# SOC_LPC1787.net
KiCad netlist of a schematic drawn in Altium Designer
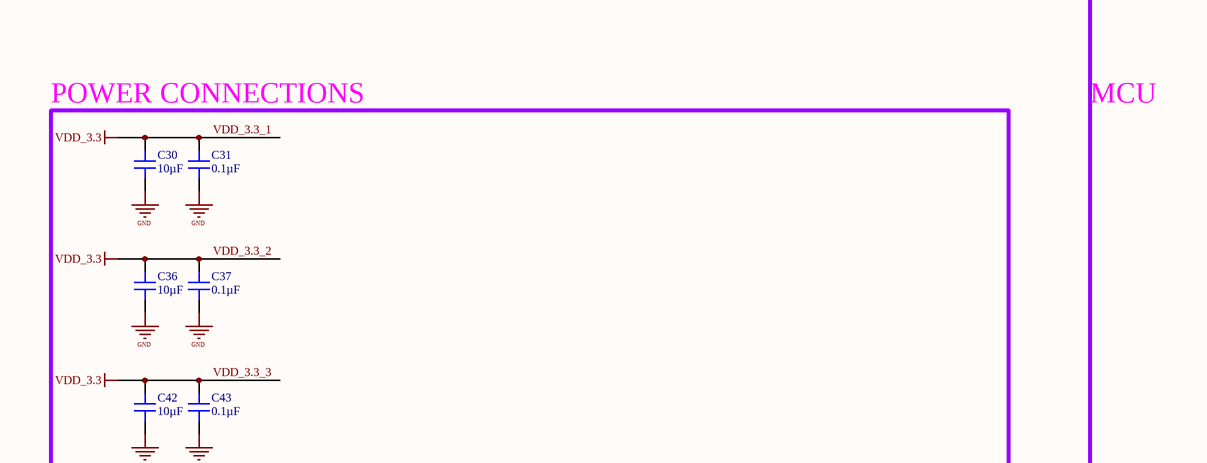
[diagram p0: SOC LPC1787.SchDoc, top left]
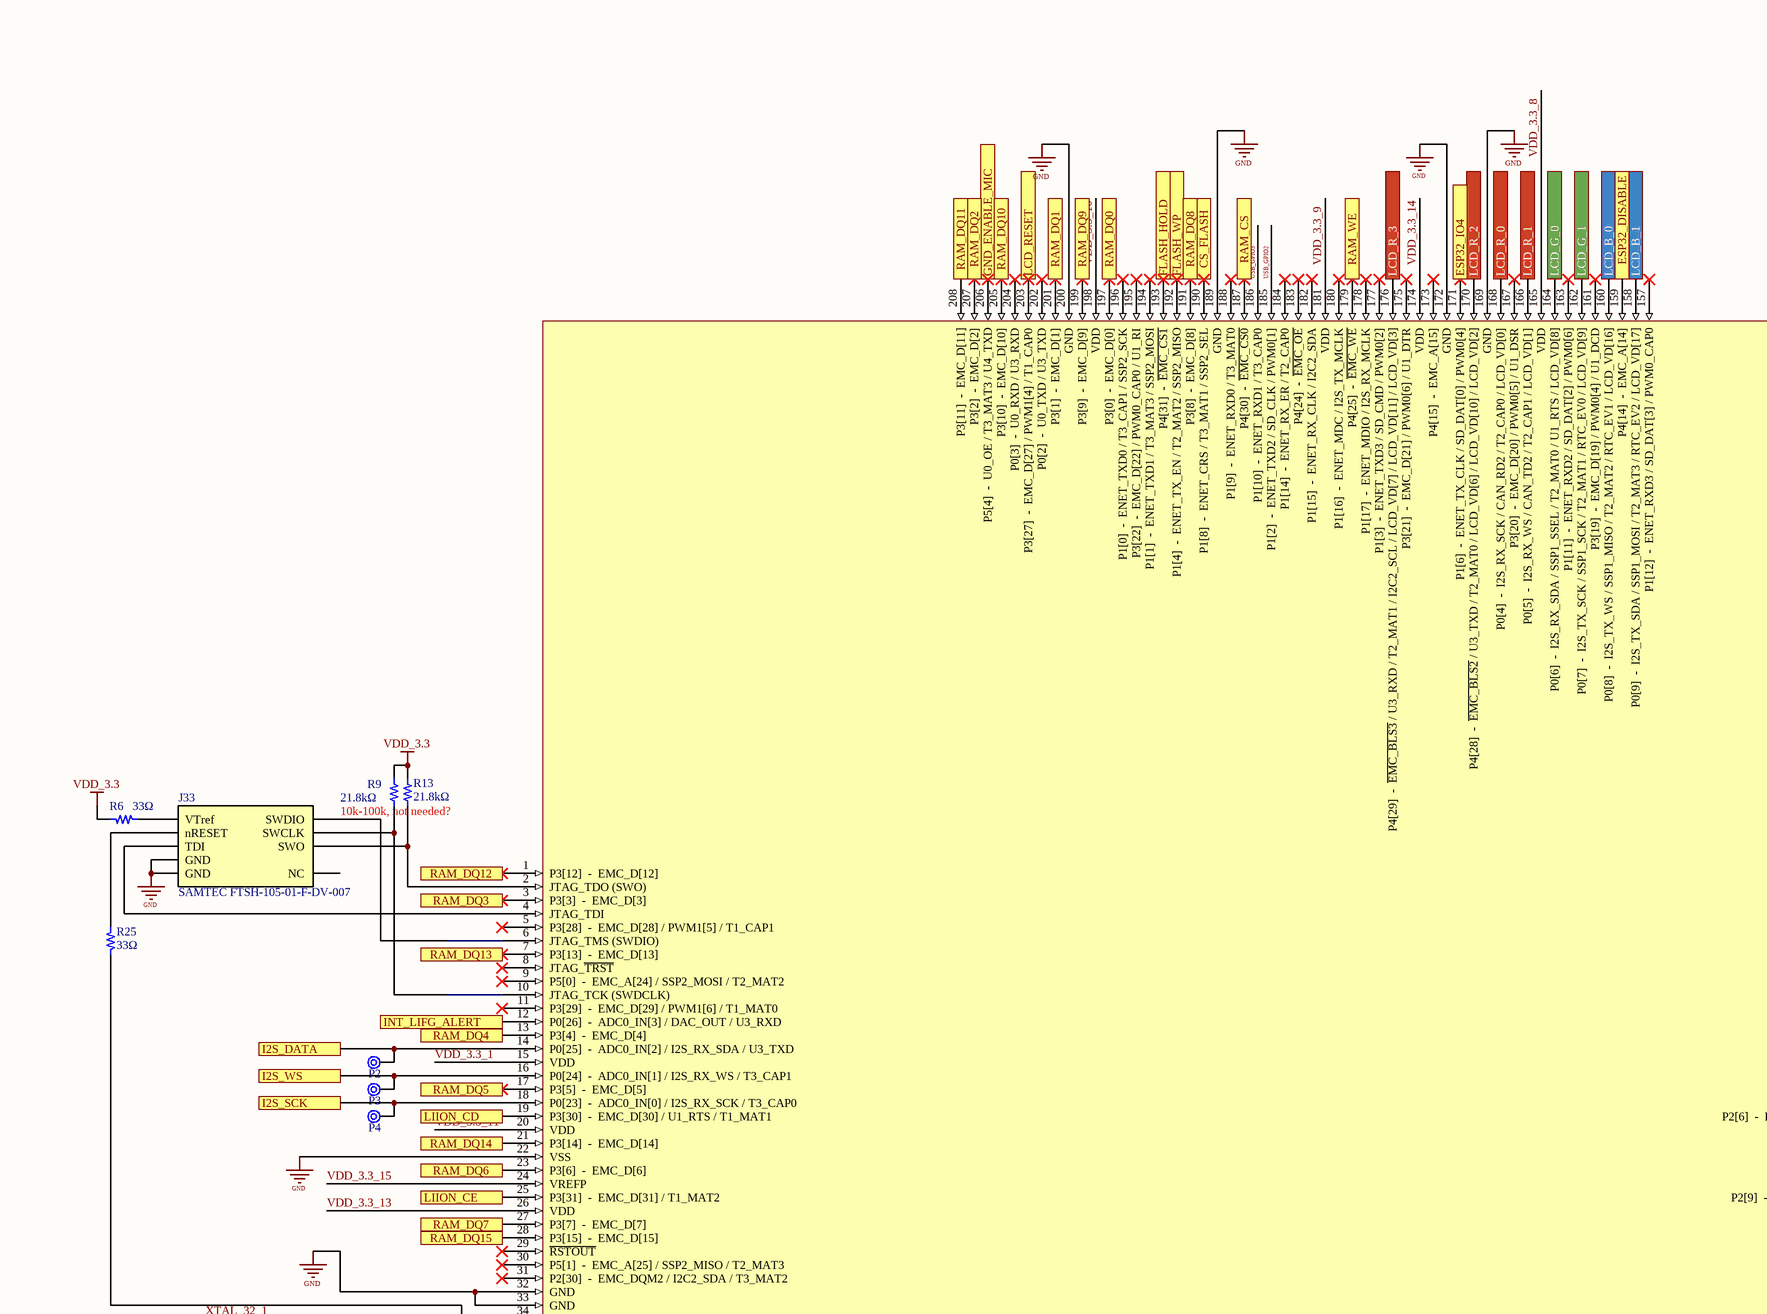
[diagram p1: SOC LPC1787.SchDoc, top middle]
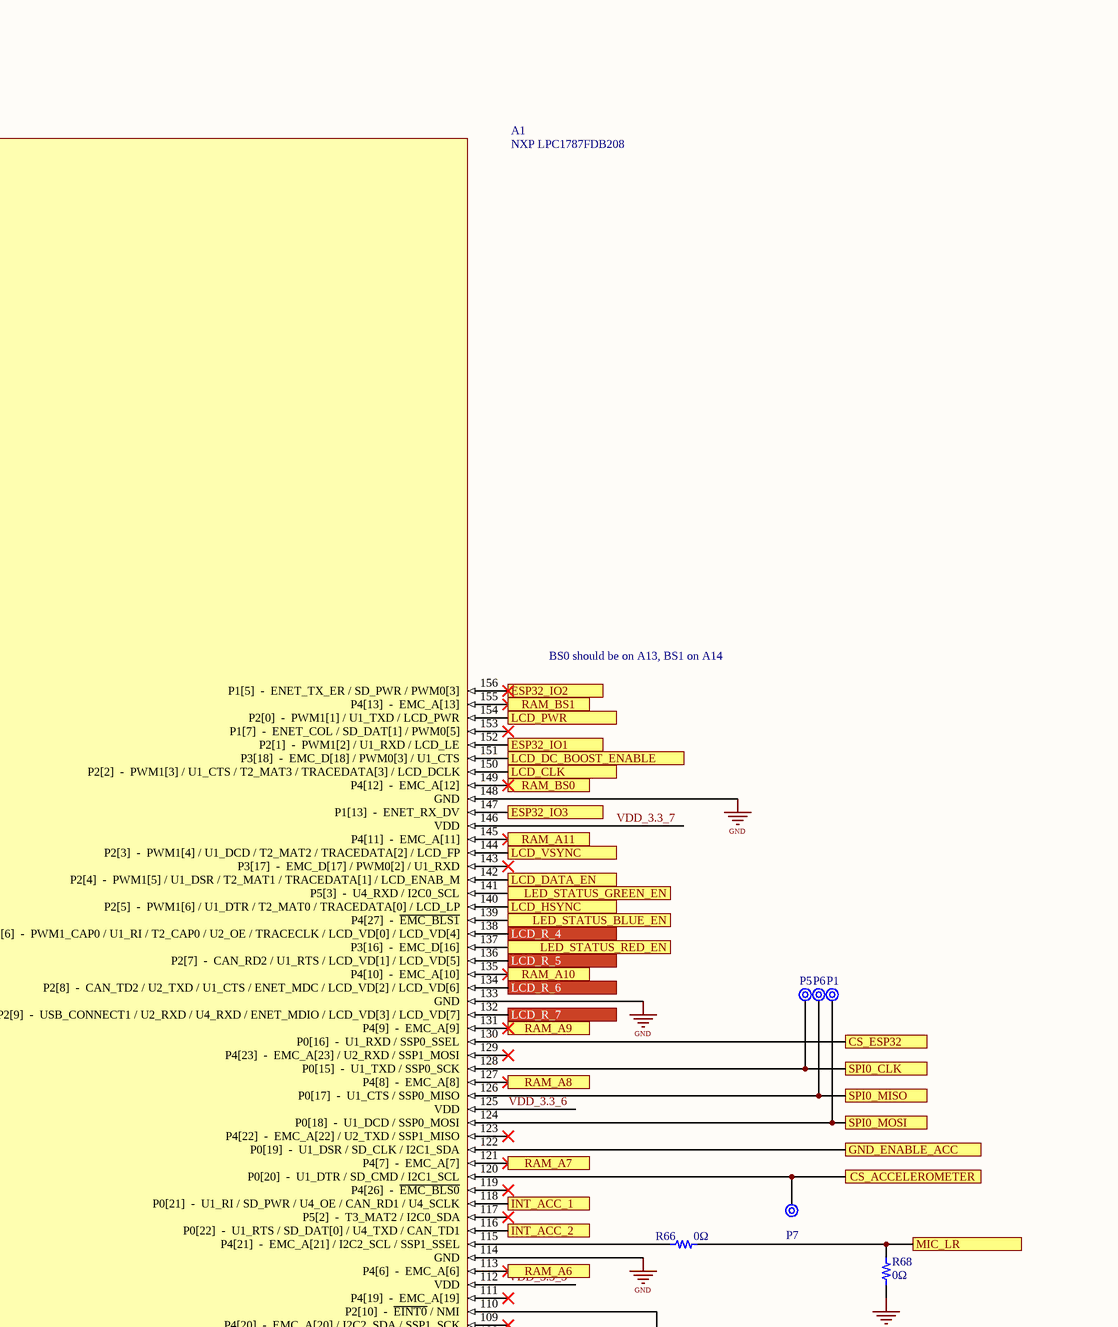
[diagram p2: SOC LPC1787.SchDoc, top right]
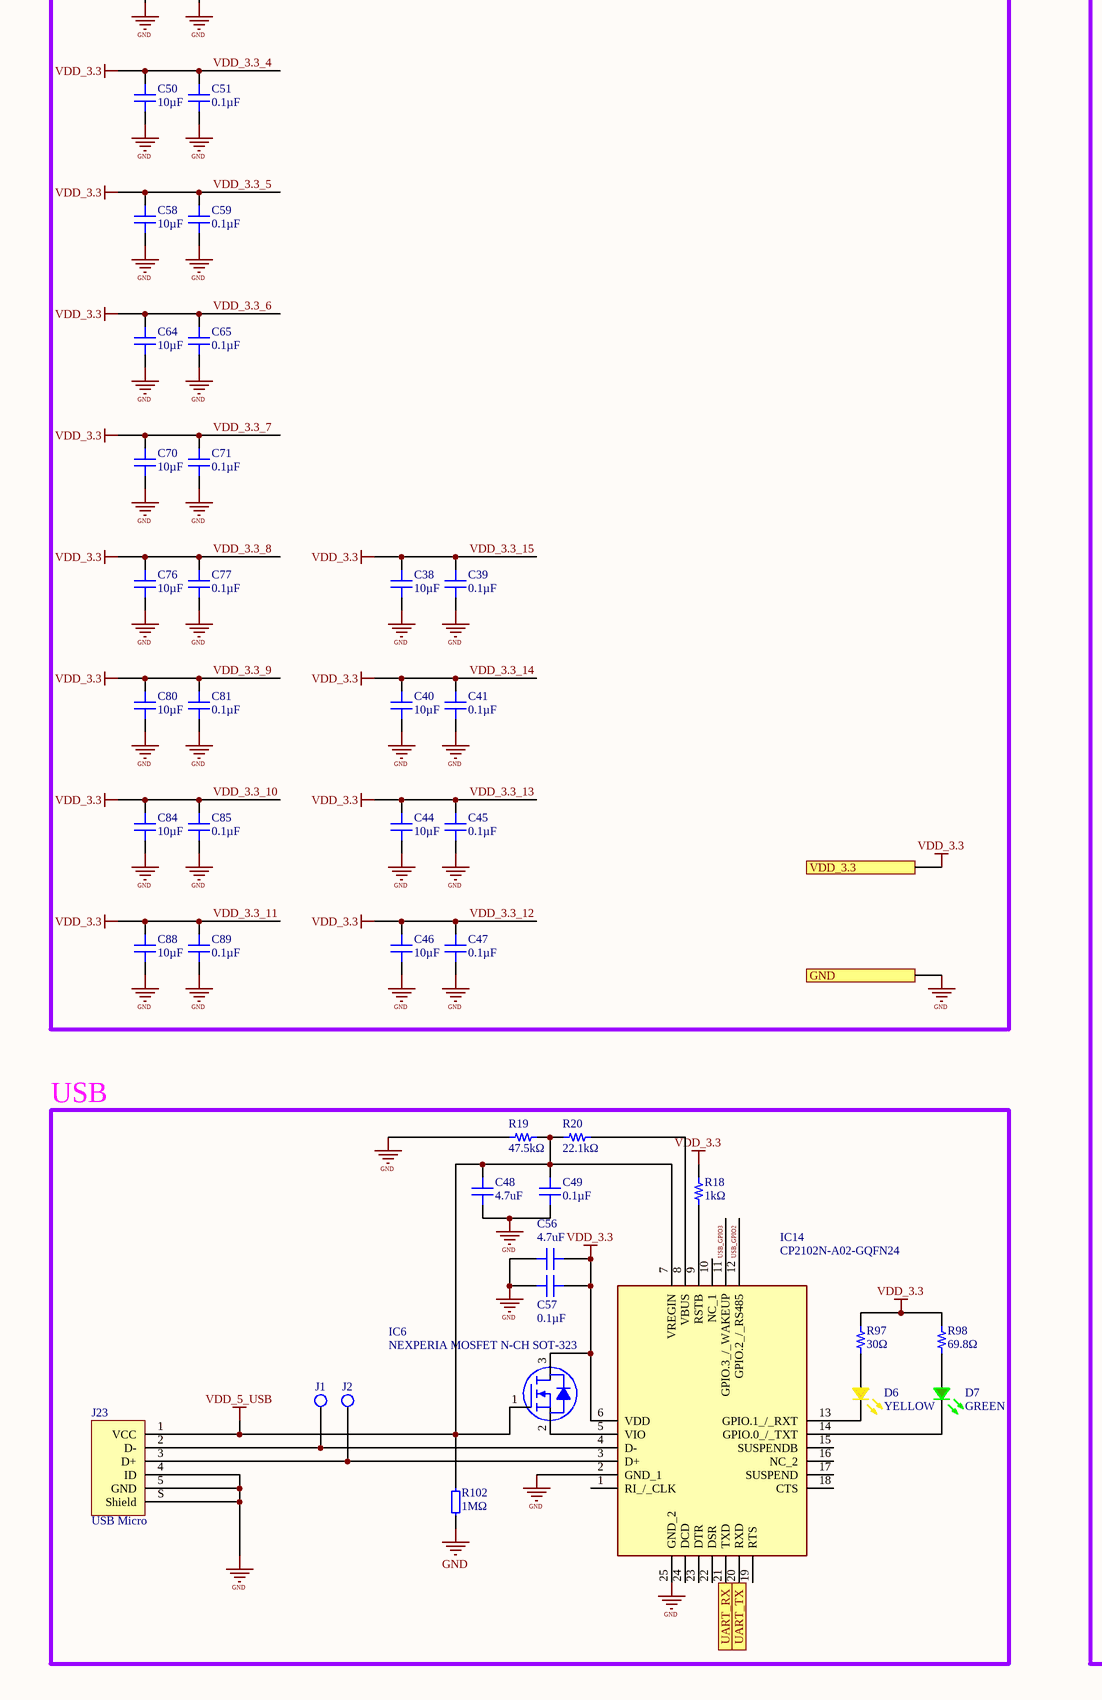
[diagram p3: SOC LPC1787.SchDoc, bottom left]
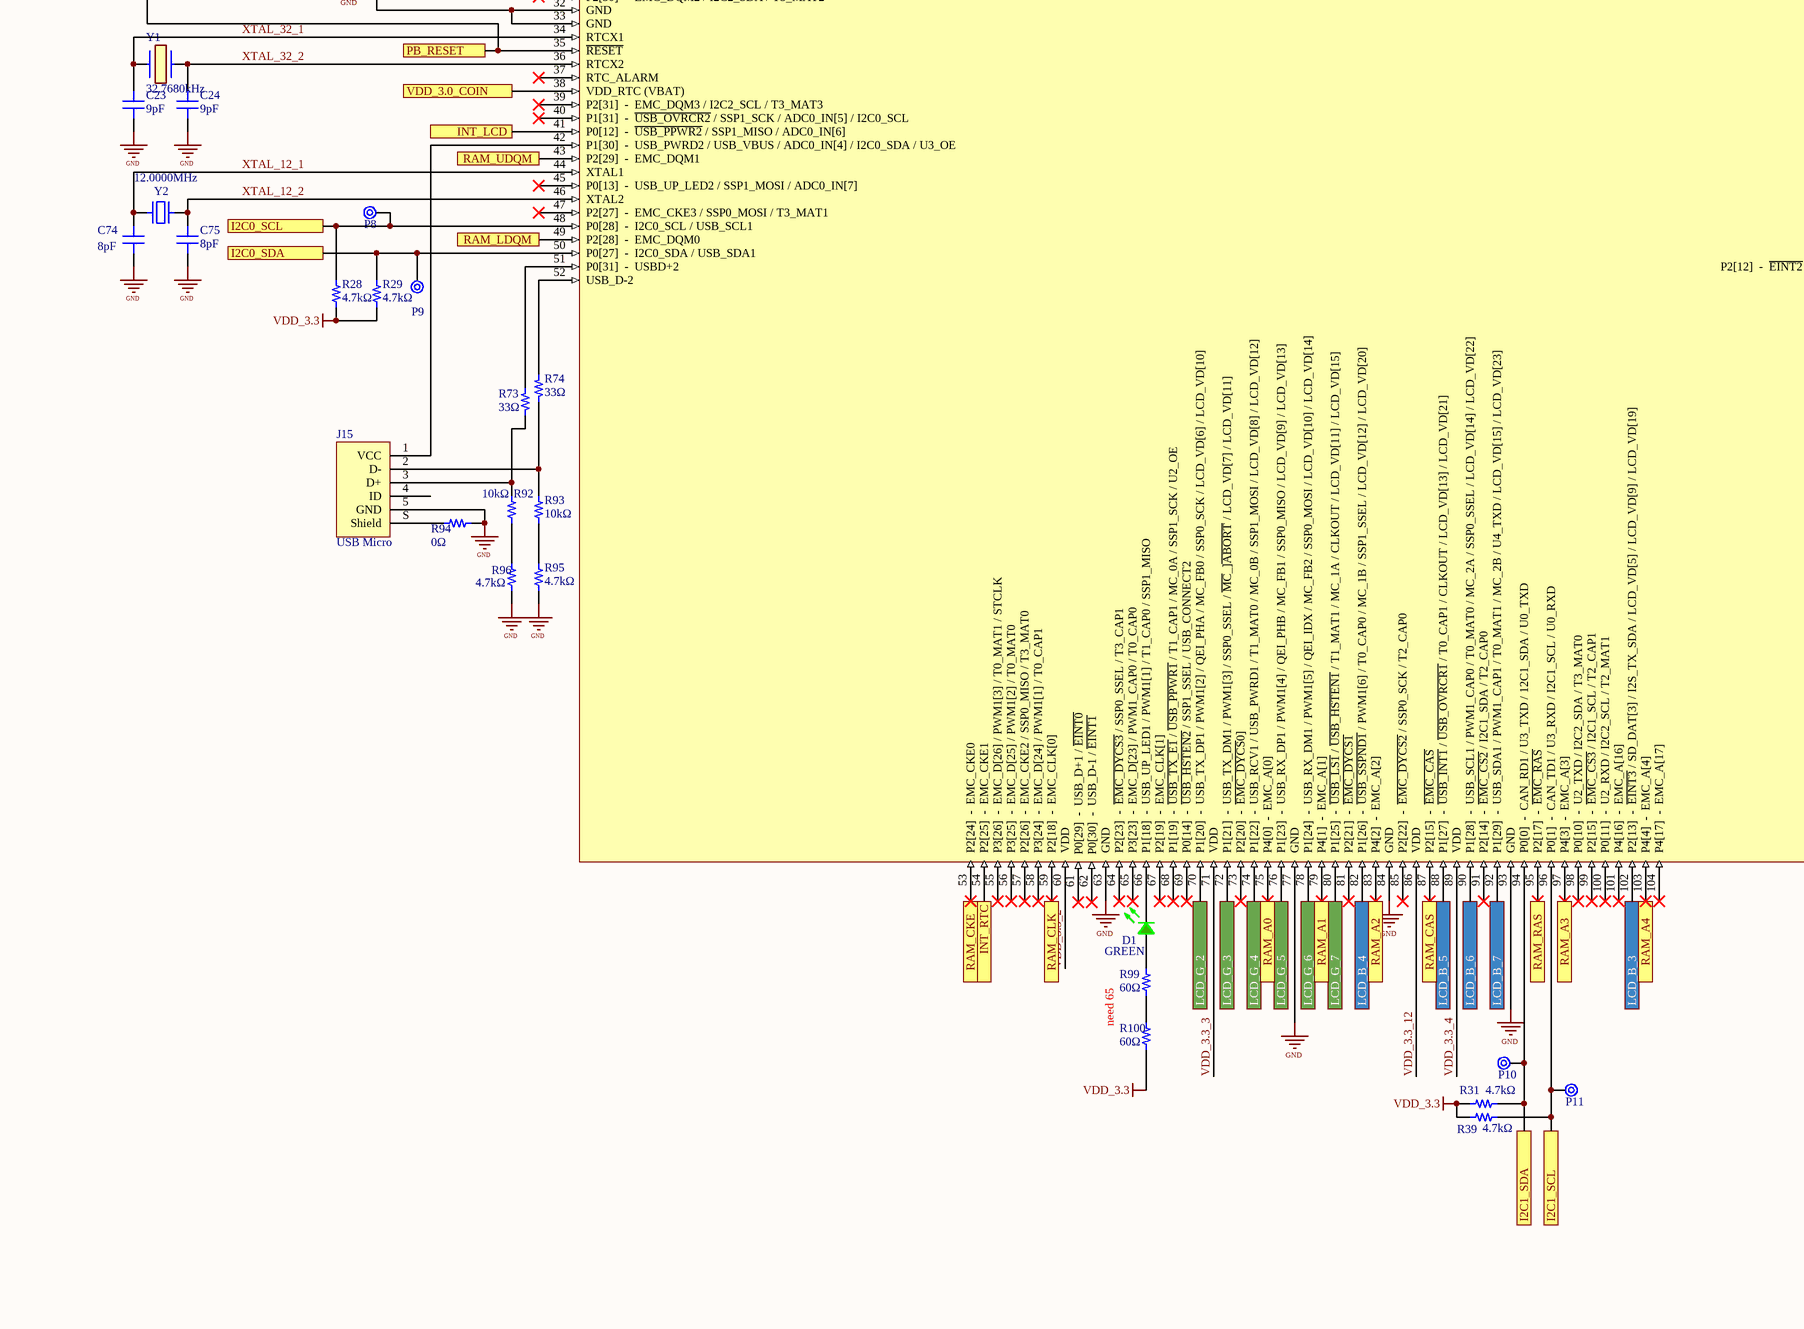
[diagram p4: SOC LPC1787.SchDoc, bottom middle]
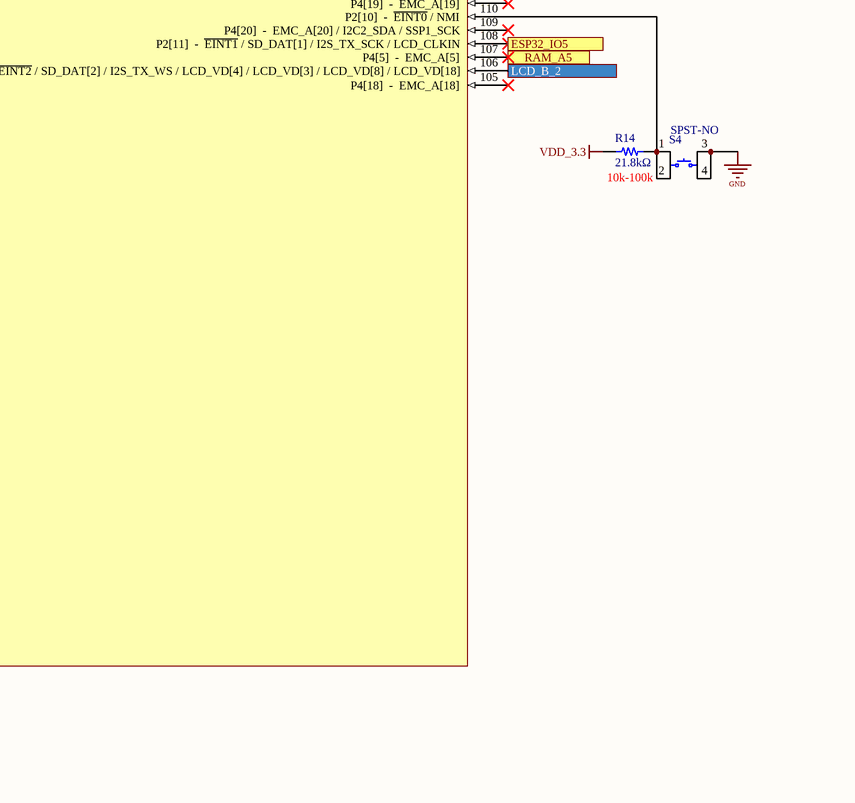
[diagram p5: SOC LPC1787.SchDoc, bottom right]

(export (version "E")
  (design (tool "Eeschema 10.0.6"))
  (components
    (comp (ref "A1")
      (value "NXP LPC1787FDB208")
      (footprint "NXP LPC1787FDB208")
      (fields (field (name "MANUFACTURER") "NXP"))
      (libsource (lib "MVVVMAltiumDatabase") (part "NXP LPC1787FDB208"))
    )
    (comp (ref "C23")
      (value "9pF")
      (footprint "CAP 0402_1005")
      (description "CAP CER 9PF 50V NPO 0402")
      (fields (field (name "MANUFACTURER") "Walsin") (field (name "VOLTAGE") "50V"))
      (libsource (lib "MVVVMAltiumDatabase") (part "Capacitor"))
    )
    (comp (ref "C24")
      (value "9pF")
      (footprint "CAP 0402_1005")
      (description "CAP CER 9PF 50V NPO 0402")
      (fields (field (name "MANUFACTURER") "Walsin") (field (name "VOLTAGE") "50V"))
      (libsource (lib "MVVVMAltiumDatabase") (part "Capacitor"))
    )
    (comp (ref "C30")
      (value "10µF")
      (footprint "CAP 0603_1608")
      (description "CAP CER 010UF 25V X7R 0603")
      (fields (field (name "MANUFACTURER") "KEMET") (field (name "VOLTAGE") "25V"))
      (libsource (lib "MVVVMAltiumDatabase") (part "Capacitor"))
    )
    (comp (ref "C31")
      (value "0.1µF")
      (footprint "CAP 0603_1608 RF")
      (description "CAP CER 0.1UF 16V X7R 0603")
      (fields (field (name "MANUFACTURER") "KEMET") (field (name "VOLTAGE") "16V"))
      (libsource (lib "MVVVMAltiumDatabase") (part "Capacitor"))
    )
    (comp (ref "C36")
      (value "10µF")
      (footprint "CAP 0603_1608")
      (description "CAP CER 010UF 25V X7R 0603")
      (fields (field (name "MANUFACTURER") "KEMET") (field (name "VOLTAGE") "25V"))
      (libsource (lib "MVVVMAltiumDatabase") (part "Capacitor"))
    )
    (comp (ref "C37")
      (value "0.1µF")
      (footprint "CAP 0603_1608 RF")
      (description "CAP CER 0.1UF 16V X7R 0603")
      (fields (field (name "MANUFACTURER") "KEMET") (field (name "VOLTAGE") "16V"))
      (libsource (lib "MVVVMAltiumDatabase") (part "Capacitor"))
    )
    (comp (ref "C38")
      (value "10µF")
      (footprint "CAP 0603_1608")
      (description "CAP CER 010UF 25V X7R 0603")
      (fields (field (name "MANUFACTURER") "KEMET") (field (name "VOLTAGE") "25V"))
      (libsource (lib "MVVVMAltiumDatabase") (part "Capacitor"))
    )
    (comp (ref "C39")
      (value "0.1µF")
      (footprint "CAP 0603_1608 RF")
      (description "CAP CER 0.1UF 16V X7R 0603")
      (fields (field (name "MANUFACTURER") "KEMET") (field (name "VOLTAGE") "16V"))
      (libsource (lib "MVVVMAltiumDatabase") (part "Capacitor"))
    )
    (comp (ref "C40")
      (value "10µF")
      (footprint "CAP 0603_1608")
      (description "CAP CER 010UF 25V X7R 0603")
      (fields (field (name "MANUFACTURER") "KEMET") (field (name "VOLTAGE") "25V"))
      (libsource (lib "MVVVMAltiumDatabase") (part "Capacitor"))
    )
    (comp (ref "C41")
      (value "0.1µF")
      (footprint "CAP 0603_1608 RF")
      (description "CAP CER 0.1UF 16V X7R 0603")
      (fields (field (name "MANUFACTURER") "KEMET") (field (name "VOLTAGE") "16V"))
      (libsource (lib "MVVVMAltiumDatabase") (part "Capacitor"))
    )
    (comp (ref "C42")
      (value "10µF")
      (footprint "CAP 0603_1608")
      (description "CAP CER 010UF 25V X7R 0603")
      (fields (field (name "MANUFACTURER") "KEMET") (field (name "VOLTAGE") "25V"))
      (libsource (lib "MVVVMAltiumDatabase") (part "Capacitor"))
    )
    (comp (ref "C43")
      (value "0.1µF")
      (footprint "CAP 0603_1608 RF")
      (description "CAP CER 0.1UF 16V X7R 0603")
      (fields (field (name "MANUFACTURER") "KEMET") (field (name "VOLTAGE") "16V"))
      (libsource (lib "MVVVMAltiumDatabase") (part "Capacitor"))
    )
    (comp (ref "C44")
      (value "10µF")
      (footprint "CAP 0603_1608")
      (description "CAP CER 010UF 25V X7R 0603")
      (fields (field (name "MANUFACTURER") "KEMET") (field (name "VOLTAGE") "25V"))
      (libsource (lib "MVVVMAltiumDatabase") (part "Capacitor"))
    )
    (comp (ref "C45")
      (value "0.1µF")
      (footprint "CAP 0603_1608 RF")
      (description "CAP CER 0.1UF 16V X7R 0603")
      (fields (field (name "MANUFACTURER") "KEMET") (field (name "VOLTAGE") "16V"))
      (libsource (lib "MVVVMAltiumDatabase") (part "Capacitor"))
    )
    (comp (ref "C46")
      (value "10µF")
      (footprint "CAP 0603_1608")
      (description "CAP CER 010UF 25V X7R 0603")
      (fields (field (name "MANUFACTURER") "KEMET") (field (name "VOLTAGE") "25V"))
      (libsource (lib "MVVVMAltiumDatabase") (part "Capacitor"))
    )
    (comp (ref "C47")
      (value "0.1µF")
      (footprint "CAP 0603_1608 RF")
      (description "CAP CER 0.1UF 16V X7R 0603")
      (fields (field (name "MANUFACTURER") "KEMET") (field (name "VOLTAGE") "16V"))
      (libsource (lib "MVVVMAltiumDatabase") (part "Capacitor"))
    )
    (comp (ref "C48")
      (value "4.7uF")
      (footprint "CAP 0603_1608")
      (description "CAP CER 4.7UF 50V X7R 0603")
      (fields (field (name "MANUFACTURER") "KEMET") (field (name "VOLTAGE") "25V"))
      (libsource (lib "MVVVMAltiumDatabase") (part "Capacitor"))
    )
    (comp (ref "C49")
      (value "0.1µF")
      (footprint "CAP 0603_1608 RF")
      (description "CAP CER 0.1UF 16V X7R 0603")
      (fields (field (name "MANUFACTURER") "KEMET") (field (name "VOLTAGE") "16V"))
      (libsource (lib "MVVVMAltiumDatabase") (part "Capacitor"))
    )
    (comp (ref "C50")
      (value "10µF")
      (footprint "CAP 0603_1608")
      (description "CAP CER 010UF 25V X7R 0603")
      (fields (field (name "MANUFACTURER") "KEMET") (field (name "VOLTAGE") "25V"))
      (libsource (lib "MVVVMAltiumDatabase") (part "Capacitor"))
    )
    (comp (ref "C51")
      (value "0.1µF")
      (footprint "CAP 0603_1608 RF")
      (description "CAP CER 0.1UF 16V X7R 0603")
      (fields (field (name "MANUFACTURER") "KEMET") (field (name "VOLTAGE") "16V"))
      (libsource (lib "MVVVMAltiumDatabase") (part "Capacitor"))
    )
    (comp (ref "C56")
      (value "4.7uF")
      (footprint "CAP 0603_1608")
      (description "CAP CER 4.7UF 50V X7R 0603")
      (fields (field (name "MANUFACTURER") "KEMET") (field (name "VOLTAGE") "25V"))
      (libsource (lib "MVVVMAltiumDatabase") (part "Capacitor"))
    )
    (comp (ref "C57")
      (value "0.1µF")
      (footprint "CAP 0603_1608 RF")
      (description "CAP CER 0.1UF 16V X7R 0603")
      (fields (field (name "MANUFACTURER") "KEMET") (field (name "VOLTAGE") "16V"))
      (libsource (lib "MVVVMAltiumDatabase") (part "Capacitor"))
    )
    (comp (ref "C58")
      (value "10µF")
      (footprint "CAP 0603_1608")
      (description "CAP CER 010UF 25V X7R 0603")
      (fields (field (name "MANUFACTURER") "KEMET") (field (name "VOLTAGE") "25V"))
      (libsource (lib "MVVVMAltiumDatabase") (part "Capacitor"))
    )
    (comp (ref "C59")
      (value "0.1µF")
      (footprint "CAP 0603_1608 RF")
      (description "CAP CER 0.1UF 16V X7R 0603")
      (fields (field (name "MANUFACTURER") "KEMET") (field (name "VOLTAGE") "16V"))
      (libsource (lib "MVVVMAltiumDatabase") (part "Capacitor"))
    )
    (comp (ref "C64")
      (value "10µF")
      (footprint "CAP 0603_1608")
      (description "CAP CER 010UF 25V X7R 0603")
      (fields (field (name "MANUFACTURER") "KEMET") (field (name "VOLTAGE") "25V"))
      (libsource (lib "MVVVMAltiumDatabase") (part "Capacitor"))
    )
    (comp (ref "C65")
      (value "0.1µF")
      (footprint "CAP 0603_1608 RF")
      (description "CAP CER 0.1UF 16V X7R 0603")
      (fields (field (name "MANUFACTURER") "KEMET") (field (name "VOLTAGE") "16V"))
      (libsource (lib "MVVVMAltiumDatabase") (part "Capacitor"))
    )
    (comp (ref "C70")
      (value "10µF")
      (footprint "CAP 0603_1608")
      (description "CAP CER 010UF 25V X7R 0603")
      (fields (field (name "MANUFACTURER") "KEMET") (field (name "VOLTAGE") "25V"))
      (libsource (lib "MVVVMAltiumDatabase") (part "Capacitor"))
    )
    (comp (ref "C71")
      (value "0.1µF")
      (footprint "CAP 0603_1608 RF")
      (description "CAP CER 0.1UF 16V X7R 0603")
      (fields (field (name "MANUFACTURER") "KEMET") (field (name "VOLTAGE") "16V"))
      (libsource (lib "MVVVMAltiumDatabase") (part "Capacitor"))
    )
    (comp (ref "C74")
      (value "8pF")
      (footprint "CAP 0402_1005")
      (description "CAP CER 12.5PF 16V C0G/NP0 0402")
      (fields (field (name "MANUFACTURER") "KEMET") (field (name "VOLTAGE") "10V"))
      (libsource (lib "MVVVMAltiumDatabase") (part "Capacitor"))
    )
    (comp (ref "C75")
      (value "8pF")
      (footprint "CAP 0402_1005")
      (description "CAP CER 12.5PF 16V C0G/NP0 0402")
      (fields (field (name "MANUFACTURER") "KEMET") (field (name "VOLTAGE") "10V"))
      (libsource (lib "MVVVMAltiumDatabase") (part "Capacitor"))
    )
    (comp (ref "C76")
      (value "10µF")
      (footprint "CAP 0603_1608")
      (description "CAP CER 010UF 25V X7R 0603")
      (fields (field (name "MANUFACTURER") "KEMET") (field (name "VOLTAGE") "25V"))
      (libsource (lib "MVVVMAltiumDatabase") (part "Capacitor"))
    )
    (comp (ref "C77")
      (value "0.1µF")
      (footprint "CAP 0603_1608 RF")
      (description "CAP CER 0.1UF 16V X7R 0603")
      (fields (field (name "MANUFACTURER") "KEMET") (field (name "VOLTAGE") "16V"))
      (libsource (lib "MVVVMAltiumDatabase") (part "Capacitor"))
    )
    (comp (ref "C80")
      (value "10µF")
      (footprint "CAP 0603_1608")
      (description "CAP CER 010UF 25V X7R 0603")
      (fields (field (name "MANUFACTURER") "KEMET") (field (name "VOLTAGE") "25V"))
      (libsource (lib "MVVVMAltiumDatabase") (part "Capacitor"))
    )
    (comp (ref "C81")
      (value "0.1µF")
      (footprint "CAP 0603_1608 RF")
      (description "CAP CER 0.1UF 16V X7R 0603")
      (fields (field (name "MANUFACTURER") "KEMET") (field (name "VOLTAGE") "16V"))
      (libsource (lib "MVVVMAltiumDatabase") (part "Capacitor"))
    )
    (comp (ref "C84")
      (value "10µF")
      (footprint "CAP 0603_1608")
      (description "CAP CER 010UF 25V X7R 0603")
      (fields (field (name "MANUFACTURER") "KEMET") (field (name "VOLTAGE") "25V"))
      (libsource (lib "MVVVMAltiumDatabase") (part "Capacitor"))
    )
    (comp (ref "C85")
      (value "0.1µF")
      (footprint "CAP 0603_1608 RF")
      (description "CAP CER 0.1UF 16V X7R 0603")
      (fields (field (name "MANUFACTURER") "KEMET") (field (name "VOLTAGE") "16V"))
      (libsource (lib "MVVVMAltiumDatabase") (part "Capacitor"))
    )
    (comp (ref "C88")
      (value "10µF")
      (footprint "CAP 0603_1608")
      (description "CAP CER 010UF 25V X7R 0603")
      (fields (field (name "MANUFACTURER") "KEMET") (field (name "VOLTAGE") "25V"))
      (libsource (lib "MVVVMAltiumDatabase") (part "Capacitor"))
    )
    (comp (ref "C89")
      (value "0.1µF")
      (footprint "CAP 0603_1608 RF")
      (description "CAP CER 0.1UF 16V X7R 0603")
      (fields (field (name "MANUFACTURER") "KEMET") (field (name "VOLTAGE") "16V"))
      (libsource (lib "MVVVMAltiumDatabase") (part "Capacitor"))
    )
    (comp (ref "D1")
      (value "GREEN")
      (footprint "LED 0603_1608")
      (description "LED RED CLEAR 0603 SMD")
      (fields (field (name "MANUFACTURER") "Würth Elektronik"))
      (libsource (lib "MVVVMAltiumDatabase") (part "LED_GREEN"))
    )
    (comp (ref "D6")
      (value "YELLOW")
      (footprint "LED 0603_1608")
      (description "LED RED CLEAR 0603 SMD")
      (fields (field (name "MANUFACTURER") "Würth Elektronik"))
      (libsource (lib "MVVVMAltiumDatabase") (part "LED_YELLOW"))
    )
    (comp (ref "D7")
      (value "GREEN")
      (footprint "LED 0603_1608")
      (description "LED RED CLEAR 0603 SMD")
      (fields (field (name "MANUFACTURER") "Würth Elektronik"))
      (libsource (lib "MVVVMAltiumDatabase") (part "LED_GREEN"))
    )
    (comp (ref "IC6")
      (value "NEXPERIA MOSFET N-CH SOT-323")
      (footprint "NEXPERIA SOT-323")
      (description "MOSFET N-CH 60V 320MA SOT323")
      (fields (field (name "MANUFACTURER") "Nexperia USA Inc."))
      (libsource (lib "MVVVMAltiumDatabase") (part "NEXPERIA MOSFET N-CH SOT-323"))
    )
    (comp (ref "IC14")
      (value "CP2102N-A02-GQFN24")
      (footprint "SamacSys:QFN50P400X400X80-25N-D")
      (description "Integrated Circuit")
      (fields (field (name "MOUSER2 PART NUMBER") "634-CP2102NA02GQFN24"))
      (libsource (lib "*") (part "CP2102N-A02-GQFN24"))
    )
    (comp (ref "J1")
      (value "TEST POINT")
      (footprint "TEST POINT")
      (libsource (lib "MVVVMAltiumDatabase") (part "TEST POINT"))
    )
    (comp (ref "J2")
      (value "TEST POINT")
      (footprint "TEST POINT")
      (libsource (lib "MVVVMAltiumDatabase") (part "TEST POINT"))
    )
    (comp (ref "J15")
      (value "USB Micro")
      (footprint "MICRO USB B")
      (fields (field (name "MANUFACTURER") "TE"))
      (libsource (lib "MVVVMAltiumDatabase") (part "USB 2.0 Type B Micro"))
    )
    (comp (ref "J23")
      (value "USB Micro")
      (footprint "MICRO USB B")
      (fields (field (name "MANUFACTURER") "TE"))
      (libsource (lib "MVVVMAltiumDatabase") (part "USB 2.0 Type B Micro"))
    )
    (comp (ref "J33")
      (value "SAMTEC FTSH-105-01-F-DV-007")
      (footprint "SAMTEC_FTSH-105-01-F-DV-007")
      (description "Connector Header Surface Mount 10 position 0.050 (1.27mm)")
      (fields (field (name "MF") "Samtec") (field (name "DIGI-KEY_PART_NUMBER") "SAM13926TR-ND"))
      (libsource (lib "MVVVMAltiumDatabase") (part "SAMTEC FTSH-105-01-F-DV-007"))
    )
    (comp (ref "P1")
      (value "1 Pin")
      (footprint "1PINTHRU")
      (libsource (lib "MVVVMAltiumDatabase") (part "1 PIN THRU"))
    )
    (comp (ref "P2")
      (value "1 Pin")
      (footprint "1PINTHRU")
      (libsource (lib "MVVVMAltiumDatabase") (part "1 PIN THRU"))
    )
    (comp (ref "P3")
      (value "1 Pin")
      (footprint "1PINTHRU")
      (libsource (lib "MVVVMAltiumDatabase") (part "1 PIN THRU"))
    )
    (comp (ref "P4")
      (value "1 Pin")
      (footprint "1PINTHRU")
      (libsource (lib "MVVVMAltiumDatabase") (part "1 PIN THRU"))
    )
    (comp (ref "P5")
      (value "1 Pin")
      (footprint "1PINTHRU")
      (libsource (lib "MVVVMAltiumDatabase") (part "1 PIN THRU"))
    )
    (comp (ref "P6")
      (value "1 Pin")
      (footprint "1PINTHRU")
      (libsource (lib "MVVVMAltiumDatabase") (part "1 PIN THRU"))
    )
    (comp (ref "P7")
      (value "1 Pin")
      (footprint "1PINTHRU")
      (libsource (lib "MVVVMAltiumDatabase") (part "1 PIN THRU"))
    )
    (comp (ref "P8")
      (value "1 Pin")
      (footprint "1PINTHRU")
      (libsource (lib "MVVVMAltiumDatabase") (part "1 PIN THRU"))
    )
    (comp (ref "P9")
      (value "1 Pin")
      (footprint "1PINTHRU")
      (libsource (lib "MVVVMAltiumDatabase") (part "1 PIN THRU"))
    )
    (comp (ref "P10")
      (value "1 Pin")
      (footprint "1PINTHRU")
      (libsource (lib "MVVVMAltiumDatabase") (part "1 PIN THRU"))
    )
    (comp (ref "P11")
      (value "1 Pin")
      (footprint "1PINTHRU")
      (libsource (lib "MVVVMAltiumDatabase") (part "1 PIN THRU"))
    )
    (comp (ref "R6")
      (value "33Ω")
      (footprint "RES 0201_0603")
      (description "RES SMD 33 OHM 1% 1/20W 0201")
      (fields (field (name "MANUFACTURER") "Vishay Dale") (field (name "TOLERANCE") "±1%"))
      (libsource (lib "MVVVMAltiumDatabase") (part "Resistor"))
    )
    (comp (ref "R9")
      (value "21.8kΩ")
      (footprint "RES 0603_1608 RF")
      (description "RES 21.8k OHM 1% 1/10W 0603")
      (fields (field (name "MANUFACTURER") "Vishay Dale") (field (name "TOLERANCE") "±1%"))
      (libsource (lib "MVVVMAltiumDatabase") (part "Resistor"))
    )
    (comp (ref "R13")
      (value "21.8kΩ")
      (footprint "RES 0603_1608 RF")
      (description "RES 21.8k OHM 1% 1/10W 0603")
      (fields (field (name "MANUFACTURER") "Vishay Dale") (field (name "TOLERANCE") "±1%"))
      (libsource (lib "MVVVMAltiumDatabase") (part "Resistor"))
    )
    (comp (ref "R14")
      (value "21.8kΩ")
      (footprint "RES 0603_1608 RF")
      (description "RES 21.8k OHM 1% 1/10W 0603")
      (fields (field (name "MANUFACTURER") "Vishay Dale") (field (name "TOLERANCE") "±1%"))
      (libsource (lib "MVVVMAltiumDatabase") (part "Resistor"))
    )
    (comp (ref "R18")
      (value "1kΩ")
      (footprint "RES 0603_1608 RF")
      (description "RES SMD 1K OHM 0.1% 1/10W 0603")
      (fields (field (name "MANUFACTURER") "Susumu") (field (name "TOLERANCE") "±0.1%"))
      (libsource (lib "MVVVMAltiumDatabase") (part "Resistor"))
    )
    (comp (ref "R19")
      (value "47.5kΩ")
      (footprint "RES 0603_1608 RF")
      (description "RES 47.5k OHM 1% 1/10W 0603")
      (fields (field (name "MANUFACTURER") "Vishay Dale") (field (name "TOLERANCE") "±1%"))
      (libsource (lib "MVVVMAltiumDatabase") (part "Resistor"))
    )
    (comp (ref "R20")
      (value "22.1kΩ")
      (footprint "RES 0603_1608 RF")
      (description "RES 22.1k OHM 1% 1/10W 0603")
      (fields (field (name "MANUFACTURER") "Vishay Dale") (field (name "TOLERANCE") "±1%"))
      (libsource (lib "MVVVMAltiumDatabase") (part "Resistor"))
    )
    (comp (ref "R25")
      (value "33Ω")
      (footprint "RES 0201_0603")
      (description "RES SMD 33 OHM 1% 1/20W 0201")
      (fields (field (name "MANUFACTURER") "Vishay Dale") (field (name "TOLERANCE") "±1%"))
      (libsource (lib "MVVVMAltiumDatabase") (part "Resistor"))
    )
    (comp (ref "R28")
      (value "4.7kΩ")
      (footprint "RES 0603_1608 RF")
      (description "RES 4.7k OHM 1% 1/10W 0603")
      (fields (field (name "MANUFACTURER") "Vishay Dale") (field (name "TOLERANCE") "±1%"))
      (libsource (lib "MVVVMAltiumDatabase") (part "Resistor"))
    )
    (comp (ref "R29")
      (value "4.7kΩ")
      (footprint "RES 0603_1608 RF")
      (description "RES 4.7k OHM 1% 1/10W 0603")
      (fields (field (name "MANUFACTURER") "Vishay Dale") (field (name "TOLERANCE") "±1%"))
      (libsource (lib "MVVVMAltiumDatabase") (part "Resistor"))
    )
    (comp (ref "R31")
      (value "4.7kΩ")
      (footprint "RES 0603_1608 RF")
      (description "RES 4.7k OHM 1% 1/10W 0603")
      (fields (field (name "MANUFACTURER") "Vishay Dale") (field (name "TOLERANCE") "±1%"))
      (libsource (lib "MVVVMAltiumDatabase") (part "Resistor"))
    )
    (comp (ref "R39")
      (value "4.7kΩ")
      (footprint "RES 0603_1608 RF")
      (description "RES 4.7k OHM 1% 1/10W 0603")
      (fields (field (name "MANUFACTURER") "Vishay Dale") (field (name "TOLERANCE") "±1%"))
      (libsource (lib "MVVVMAltiumDatabase") (part "Resistor"))
    )
    (comp (ref "R66")
      (value "0Ω")
      (footprint "RES 0603_1608 RF")
      (description "RES 0 OHM 1% 1/10W 0603")
      (fields (field (name "MANUFACTURER") "Vishay Dale") (field (name "TOLERANCE") "±1%"))
      (libsource (lib "MVVVMAltiumDatabase") (part "Resistor"))
    )
    (comp (ref "R68")
      (value "0Ω")
      (footprint "RES 0603_1608 RF")
      (description "RES 0 OHM 1% 1/10W 0603")
      (fields (field (name "MANUFACTURER") "Vishay Dale") (field (name "TOLERANCE") "±1%"))
      (libsource (lib "MVVVMAltiumDatabase") (part "Resistor"))
    )
    (comp (ref "R73")
      (value "33Ω")
      (footprint "RES 0201_0603")
      (description "RES SMD 33 OHM 1% 1/20W 0201")
      (fields (field (name "MANUFACTURER") "Vishay Dale") (field (name "TOLERANCE") "±1%"))
      (libsource (lib "MVVVMAltiumDatabase") (part "Resistor"))
    )
    (comp (ref "R74")
      (value "33Ω")
      (footprint "RES 0201_0603")
      (description "RES SMD 33 OHM 1% 1/20W 0201")
      (fields (field (name "MANUFACTURER") "Vishay Dale") (field (name "TOLERANCE") "±1%"))
      (libsource (lib "MVVVMAltiumDatabase") (part "Resistor"))
    )
    (comp (ref "R92")
      (value "10kΩ")
      (footprint "RES 0603_1608 RF")
      (description "RES SMD 10K OHM 5% 1/10W 0603")
      (fields (field (name "MANUFACTURER") "Vishay Dale") (field (name "TOLERANCE") "±5%"))
      (libsource (lib "MVVVMAltiumDatabase") (part "Resistor"))
    )
    (comp (ref "R93")
      (value "10kΩ")
      (footprint "RES 0603_1608 RF")
      (description "RES SMD 10K OHM 5% 1/10W 0603")
      (fields (field (name "MANUFACTURER") "Vishay Dale") (field (name "TOLERANCE") "±5%"))
      (libsource (lib "MVVVMAltiumDatabase") (part "Resistor"))
    )
    (comp (ref "R94")
      (value "0Ω")
      (footprint "RES 0603_1608 RF")
      (description "RES 0 OHM 1% 1/10W 0603")
      (fields (field (name "MANUFACTURER") "Vishay Dale") (field (name "TOLERANCE") "±1%"))
      (libsource (lib "MVVVMAltiumDatabase") (part "Resistor"))
    )
    (comp (ref "R95")
      (value "4.7kΩ")
      (footprint "RES 0603_1608 RF")
      (description "RES 4.7k OHM 1% 1/10W 0603")
      (fields (field (name "MANUFACTURER") "Vishay Dale") (field (name "TOLERANCE") "±1%"))
      (libsource (lib "MVVVMAltiumDatabase") (part "Resistor"))
    )
    (comp (ref "R96")
      (value "4.7kΩ")
      (footprint "RES 0603_1608 RF")
      (description "RES 4.7k OHM 1% 1/10W 0603")
      (fields (field (name "MANUFACTURER") "Vishay Dale") (field (name "TOLERANCE") "±1%"))
      (libsource (lib "MVVVMAltiumDatabase") (part "Resistor"))
    )
    (comp (ref "R97")
      (value "30Ω")
      (footprint "RES 0603_1608 RF")
      (description "RES 30 OHM 1% 1/10W 0603")
      (fields (field (name "MANUFACTURER") "Vishay Dale") (field (name "TOLERANCE") "±1%"))
      (libsource (lib "MVVVMAltiumDatabase") (part "Resistor"))
    )
    (comp (ref "R98")
      (value "69.8Ω")
      (footprint "RES 0603_1608 RF")
      (description "RES 69.8 OHM 1% 1/10W 0603")
      (fields (field (name "MANUFACTURER") "Vishay Dale") (field (name "TOLERANCE") "±1%"))
      (libsource (lib "MVVVMAltiumDatabase") (part "Resistor"))
    )
    (comp (ref "R99")
      (value "60Ω")
      (footprint "RES 0603_1608 RF")
      (description "RES 60 OHM 1% 1/10W 0603")
      (fields (field (name "MANUFACTURER") "Vishay Dale") (field (name "TOLERANCE") "±1%"))
      (libsource (lib "MVVVMAltiumDatabase") (part "Resistor"))
    )
    (comp (ref "R100")
      (value "60Ω")
      (footprint "RES 0603_1608 RF")
      (description "RES 60 OHM 1% 1/10W 0603")
      (fields (field (name "MANUFACTURER") "Vishay Dale") (field (name "TOLERANCE") "±1%"))
      (libsource (lib "MVVVMAltiumDatabase") (part "Resistor"))
    )
    (comp (ref "R102")
      (value "1MΩ")
      (footprint "0603_1608 RF")
      (description "0603 RF Passive")
      (libsource (lib "MVVVMAltiumDatabase") (part "RF Passive"))
    )
    (comp (ref "S4")
      (value "SPST-NO")
      (footprint "TE FSM4JSMA")
      (description "SWITCH TACTILE SPST-NO 0.05A 24V")
      (fields (field (name "MANUFACTURER") "TE Connectivity ALCOSWITCH Switches"))
      (libsource (lib "MVVVMAltiumDatabase") (part "TE FSM4JSMA"))
    )
    (comp (ref "Y1")
      (value "32.7680kHz")
      (footprint "EPSON FC135R")
      (description "CRYSTAL 32.7680KHZ 9PF SMD")
      (fields (field (name "MANUFACTURER") "EPSON") (field (name "TOLERANCE") "±10ppm"))
      (libsource (lib "MVVVMAltiumDatabase") (part "EPSON CRYSTAL FC135R"))
    )
    (comp (ref "Y2")
      (value "12.0000MHz")
      (footprint "ECX 53B")
      (description "CRYSTAL 32.7680KHZ 12.5PF SMD")
      (fields (field (name "MANUFACTURER") "ECS") (field (name "TOLERANCE") "±10ppm"))
      (libsource (lib "MVVVMAltiumDatabase") (part "ECX CRYSTAL 53B"))
    )
  )
  (nets
    (net (code "1") (name "/CS_ACCELEROMETER") (class "Default")
      (node (ref "A1") (pin "120") (pinfunction "P0[20]__-__U1_DTR_/_SD_CMD_/_I2C1_SCL_120") (pintype "input"))
      (node (ref "P7") (pin "1") (pinfunction "PAD_1") (pintype "passive"))
    )
    (net (code "2") (name "/CS_ESP32") (class "Default")
      (node (ref "A1") (pin "130") (pinfunction "P0[16]__-__U1_RXD_/_SSP0_SSEL_130") (pintype "input"))
    )
    (net (code "3") (name "/CS_FLASH") (class "Default")
      (node (ref "A1") (pin "190") (pinfunction "P1[8]__-__ENET_CRS_/_T3_MAT1_/_SSP2_SEL_190") (pintype "input+no_connect"))
    )
    (net (code "4") (name "/ESP32_DISABLE") (class "Default")
      (node (ref "A1") (pin "159") (pinfunction "P4[14]__-__EMC_A[14]_159") (pintype "input"))
    )
    (net (code "5") (name "/ESP32_IO1") (class "Default")
      (node (ref "A1") (pin "152") (pinfunction "P2[1]__-__PWM1[2]_/_U1_RXD_/_LCD_LE_152") (pintype "input"))
    )
    (net (code "6") (name "/ESP32_IO2") (class "Default")
      (node (ref "A1") (pin "156") (pinfunction "P1[5]__-__ENET_TX_ER_/_SD_PWR_/_PWM0[3]_156") (pintype "input+no_connect"))
    )
    (net (code "7") (name "/ESP32_IO3") (class "Default")
      (node (ref "A1") (pin "147") (pinfunction "P1[13]__-__ENET_RX_DV_147") (pintype "input"))
    )
    (net (code "8") (name "/ESP32_IO4") (class "Default")
      (node (ref "A1") (pin "171") (pinfunction "P1[6]__-__ENET_TX_CLK_/_SD_DAT[0]_/_PWM0[4]_171") (pintype "input+no_connect"))
    )
    (net (code "9") (name "/ESP32_IO5") (class "Default")
      (node (ref "A1") (pin "108") (pinfunction "P2[11]__-__~{EINT1}_/_SD_DAT[1]_/_I2S_TX_SCK_/_LCD_CLKIN_108") (pintype "input+no_connect"))
    )
    (net (code "10") (name "/FLASH_HOLD") (class "Default")
      (node (ref "A1") (pin "193") (pinfunction "P4[31]__-__~{EMC_CS1}_193") (pintype "input+no_connect"))
    )
    (net (code "11") (name "/FLASH_WP") (class "Default")
      (node (ref "A1") (pin "192") (pinfunction "P1[4]__-__ENET_TX_EN_/_T2_MAT2_/_SSP2_MISO_192") (pintype "input+no_connect"))
    )
    (net (code "12") (name "/GND_ENABLE_ACC") (class "Default")
      (node (ref "A1") (pin "122") (pinfunction "P0[19]__-__U1_DSR_/_SD_CLK_/_I2C1_SDA_122") (pintype "input"))
    )
    (net (code "13") (name "/GND_ENABLE_MIC") (class "Default")
      (node (ref "A1") (pin "206") (pinfunction "P5[4]__-__U0_OE_/_T3_MAT3_/_U4_TXD_206") (pintype "input+no_connect"))
    )
    (net (code "14") (name "/I2C0_SCL") (class "Default")
      (node (ref "A1") (pin "48") (pinfunction "P0[28]__-__I2C0_SCL_/_USB_SCL1_48") (pintype "input"))
      (node (ref "P8") (pin "1") (pinfunction "PAD_1") (pintype "passive"))
      (node (ref "R28") (pin "1") (pinfunction "1_1") (pintype "passive"))
    )
    (net (code "15") (name "/I2C0_SDA") (class "Default")
      (node (ref "A1") (pin "50") (pinfunction "P0[27]__-__I2C0_SDA_/_USB_SDA1_50") (pintype "input"))
      (node (ref "P9") (pin "1") (pinfunction "PAD_1") (pintype "passive"))
      (node (ref "R29") (pin "1") (pinfunction "1_1") (pintype "passive"))
    )
    (net (code "16") (name "/I2C1_SCL") (class "Default")
      (node (ref "A1") (pin "96") (pinfunction "P0[1]__-__CAN_TD1_/_U3_RXD_/_I2C1_SCL_/_U0_RXD_96") (pintype "input"))
      (node (ref "P11") (pin "1") (pinfunction "PAD_1") (pintype "passive"))
      (node (ref "R39") (pin "1") (pinfunction "1_1") (pintype "passive"))
    )
    (net (code "17") (name "/I2C1_SDA") (class "Default")
      (node (ref "A1") (pin "94") (pinfunction "P0[0]__-__CAN_RD1_/_U3_TXD_/_12C1_SDA_/_U0_TXD_94") (pintype "input"))
      (node (ref "P10") (pin "1") (pinfunction "PAD_1") (pintype "passive"))
      (node (ref "R31") (pin "1") (pinfunction "1_1") (pintype "passive"))
    )
    (net (code "18") (name "/I2S_DATA") (class "Default")
      (node (ref "A1") (pin "14") (pinfunction "P0[25]__-__ADC0_IN[2]_/_I2S_RX_SDA_/_U3_TXD_14") (pintype "input"))
      (node (ref "P2") (pin "1") (pinfunction "PAD_1") (pintype "passive"))
    )
    (net (code "19") (name "/I2S_SCK") (class "Default")
      (node (ref "A1") (pin "18") (pinfunction "P0[23]__-__ADC0_IN[0]_/_I2S_RX_SCK_/_T3_CAP0_18") (pintype "input"))
      (node (ref "P4") (pin "1") (pinfunction "PAD_1") (pintype "passive"))
    )
    (net (code "20") (name "/I2S_WS") (class "Default")
      (node (ref "A1") (pin "16") (pinfunction "P0[24]__-__ADC0_IN[1]_/_I2S_RX_WS_/_T3_CAP1_16") (pintype "input"))
      (node (ref "P3") (pin "1") (pinfunction "PAD_1") (pintype "passive"))
    )
    (net (code "21") (name "/INT_ACC_1") (class "Default")
      (node (ref "A1") (pin "118") (pinfunction "P0[21]__-__U1_RI_/_SD_PWR_/_U4_OE_/_CAN_RD1_/_U4_SCLK_118") (pintype "input"))
    )
    (net (code "22") (name "/INT_ACC_2") (class "Default")
      (node (ref "A1") (pin "116") (pinfunction "P0[22]__-__U1_RTS_/_SD_DAT[0]_/_U4_TXD_/_CAN_TD1_116") (pintype "input"))
    )
    (net (code "23") (name "/INT_LCD") (class "Default")
      (node (ref "A1") (pin "41") (pinfunction "P0[12]__-__~{USB_PPWR2}_/_SSP1_MISO_/_ADC0_IN[6]_41") (pintype "input"))
    )
    (net (code "24") (name "/INT_LIFG_ALERT") (class "Default")
      (node (ref "A1") (pin "12") (pinfunction "P0[26]__-__ADC0_IN[3]_/_DAC_OUT_/_U3_RXD_12") (pintype "input"))
    )
    (net (code "25") (name "/INT_RTC") (class "Default")
      (node (ref "A1") (pin "54") (pinfunction "P2[25]__-__EMC_CKE1_54") (pintype "input"))
    )
    (net (code "26") (name "/LCD_B_0") (class "Default")
      (node (ref "A1") (pin "160") (pinfunction "P0[8]__-__I2S_TX_WS_/_SSP1_MISO_/_T2_MAT2_/_RTC_EV1_/_LCD_VD[16]_160") (pintype "input"))
    )
    (net (code "27") (name "/LCD_B_1") (class "Default")
      (node (ref "A1") (pin "158") (pinfunction "P0[9]__-__I2S_TX_SDA_/_SSP1_MOSI_/_T2_MAT3_/_RTC_EV2_/_LCD_VD[17]_158") (pintype "input"))
    )
    (net (code "28") (name "/LCD_B_2") (class "Default")
      (node (ref "A1") (pin "106") (pinfunction "P2[12]__-__~{EINT2}_/_SD_DAT[2]_/_I2S_TX_WS_/_LCD_VD[4]_/_LCD_VD[3]_/_LCD_VD[8]_/_LCD_VD[18]_106") (pintype "input"))
    )
    (net (code "29") (name "/LCD_B_3") (class "Default")
      (node (ref "A1") (pin "102") (pinfunction "P2[13]__-__~{EINT3}_/_SD_DAT[3]_/_I2S_TX_SDA_/_LCD_VD[5]_/_LCD_VD[9]_/_LCD_VD[19]_102") (pintype "input"))
    )
    (net (code "30") (name "/LCD_B_4") (class "Default")
      (node (ref "A1") (pin "82") (pinfunction "P1[26]__-__~{USB_SSPND1}_/_PWM1[6]_/_T0_CAP0_/_MC_1B_/_SSP1_SSEL_/_LCD_VD[12]_/_LCD_VD[20]_82") (pintype "input"))
    )
    (net (code "31") (name "/LCD_B_5") (class "Default")
      (node (ref "A1") (pin "88") (pinfunction "P1[27]__-__~{USB_INT1}_/_~{USB_OVRCR1}_/_T0_CAP1_/_CLKOUT_/_LCD_VD[13]_/_LCD_VD[21]_88") (pintype "input"))
    )
    (net (code "32") (name "/LCD_B_6") (class "Default")
      (node (ref "A1") (pin "90") (pinfunction "P1[28]__-__USB_SCL1_/_PWM1_CAP0_/_T0_MAT0_/_MC_2A_/_SSP0_SSEL_/_LCD_VD[14]_/_LCD_VD[22]_90") (pintype "input"))
    )
    (net (code "33") (name "/LCD_B_7") (class "Default")
      (node (ref "A1") (pin "92") (pinfunction "P1[29]__-__USB_SDA1_/_PWM1_CAP1_/_T0_MAT1_/_MC_2B_/_U4_TXD_/_LCD_VD[15]_/_LCD_VD[23]_92") (pintype "input"))
    )
    (net (code "34") (name "/LCD_CLK") (class "Default")
      (node (ref "A1") (pin "150") (pinfunction "P2[2]__-__PWM1[3]_/_U1_CTS_/_T2_MAT3_/_TRACEDATA[3]_/_LCD_DCLK_150") (pintype "input"))
    )
    (net (code "35") (name "/LCD_DATA_EN") (class "Default")
      (node (ref "A1") (pin "142") (pinfunction "P2[4]__-__PWM1[5]_/_U1_DSR_/_T2_MAT1_/_TRACEDATA[1]_/_LCD_ENAB_M_142") (pintype "input"))
    )
    (net (code "36") (name "/LCD_DC_BOOST_ENABLE") (class "Default")
      (node (ref "A1") (pin "151") (pinfunction "P3[18]__-__EMC_D[18]_/_PWM0[3]_/_U1_CTS_151") (pintype "input"))
    )
    (net (code "37") (name "/LCD_G_0") (class "Default")
      (node (ref "A1") (pin "164") (pinfunction "P0[6]__-__I2S_RX_SDA_/_SSP1_SSEL_/_T2_MAT0_/_U1_RTS_/_LCD_VD[8]_164") (pintype "input"))
    )
    (net (code "38") (name "/LCD_G_1") (class "Default")
      (node (ref "A1") (pin "162") (pinfunction "P0[7]__-__I2S_TX_SCK_/_SSP1_SCK_/_T2_MAT1_/_RTC_EV0_/_LCD_VD[9]_162") (pintype "input"))
    )
    (net (code "39") (name "/LCD_G_2") (class "Default")
      (node (ref "A1") (pin "70") (pinfunction "P1[20]__-__USB_TX_DP1_/_PWM1[2]_/_QEI_PHA_/_MC_FB0_/_SSP0_SCK_/_LCD_VD[6]_/_LCD_VD[10]_70") (pintype "input"))
    )
    (net (code "40") (name "/LCD_G_3") (class "Default")
      (node (ref "A1") (pin "72") (pinfunction "P1[21]__-__USB_TX_DM1_/_PWM1[3]_/_SSP0_SSEL_/_~{MC}_]~{ABORT}_/_LCD_VD[7]_/_LCD_VD[11]_72") (pintype "input"))
    )
    (net (code "41") (name "/LCD_G_4") (class "Default")
      (node (ref "A1") (pin "74") (pinfunction "P1[22]__-__USB_RCV1_/_USB_PWRD1_/_T1_MAT0_/_MC_0B_/_SSP1_MOSI_/_LCD_VD[8]_/_LCD_VD[12]_74") (pintype "input"))
    )
    (net (code "42") (name "/LCD_G_5") (class "Default")
      (node (ref "A1") (pin "76") (pinfunction "P1[23]__-__USB_RX_DP1_/_PWM1[4]_/_QEI_PHB_/_MC_FB1_/_SSP0_MISO_/_LCD_VD[9]_/_LCD_VD[13]_76") (pintype "input"))
    )
    (net (code "43") (name "/LCD_G_6") (class "Default")
      (node (ref "A1") (pin "78") (pinfunction "P1[24]__-__USB_RX_DM1_/_PWM1[5]_/_QEI_IDX_/_MC_FB2_/_SSP0_MOSI_/_LCD_VD[10]_/_LCD_VD[14]_78") (pintype "input"))
    )
    (net (code "44") (name "/LCD_G_7") (class "Default")
      (node (ref "A1") (pin "80") (pinfunction "P1[25]__-__~{USB_LS1}_/_~{USB_HSTEN1}_/_T1_MAT1_/_MC_1A_/_CLKOUT_/_LCD_VD[11]_/_LCD_VD[15]_80") (pintype "input"))
    )
    (net (code "45") (name "/LCD_HSYNC") (class "Default")
      (node (ref "A1") (pin "140") (pinfunction "P2[5]__-__PWM1[6]_/_U1_DTR_/_T2_MAT0_/_TRACEDATA[0]_/_LCD_LP_140") (pintype "input"))
    )
    (net (code "46") (name "/LCD_PWR") (class "Default")
      (node (ref "A1") (pin "154") (pinfunction "P2[0]__-__PWM1[1]_/_U1_TXD_/_LCD_PWR_154") (pintype "input"))
    )
    (net (code "47") (name "/LCD_RESET") (class "Default")
      (node (ref "A1") (pin "203") (pinfunction "P3[27]__-__EMC_D[27]_/_PWM1[4]_/_T1_CAP0_203") (pintype "input+no_connect"))
    )
    (net (code "48") (name "/LCD_R_0") (class "Default")
      (node (ref "A1") (pin "168") (pinfunction "P0[4]__-__I2S_RX_SCK_/_CAN_RD2_/_T2_CAP0_/_LCD_VD[0]_168") (pintype "input"))
    )
    (net (code "49") (name "/LCD_R_1") (class "Default")
      (node (ref "A1") (pin "166") (pinfunction "P0[5]__-__I2S_RX_WS_/_CAN_TD2_/_T2_CAP1_/_LCD_VD[1]_166") (pintype "input"))
    )
    (net (code "50") (name "/LCD_R_2") (class "Default")
      (node (ref "A1") (pin "170") (pinfunction "P4[28]__-__~{EMC_BLS2}_/_U3_TXD_/_T2_MAT0_/_LCD_VD[6]_/_LCD_VD[10]_/_LCD_VD[2]_170") (pintype "input"))
    )
    (net (code "51") (name "/LCD_R_3") (class "Default")
      (node (ref "A1") (pin "176") (pinfunction "P4[29]__-__~{EMC_BLS3}_/_U3_RXD_/_T2_MAT1_/_I2C2_SCL_/_LCD_VD[7]_/_LCD_VD[11]_/_LCD_VD[3]_176") (pintype "input"))
    )
    (net (code "52") (name "/LCD_R_4") (class "Default")
      (node (ref "A1") (pin "138") (pinfunction "P2[6]__-__PWM1_CAP0_/_U1_RI_/_T2_CAP0_/_U2_OE_/_TRACECLK_/_LCD_VD[0]_/_LCD_VD[4]_138") (pintype "input"))
    )
    (net (code "53") (name "/LCD_R_5") (class "Default")
      (node (ref "A1") (pin "136") (pinfunction "P2[7]__-__CAN_RD2_/_U1_RTS_/_LCD_VD[1]_/_LCD_VD[5]_136") (pintype "input"))
    )
    (net (code "54") (name "/LCD_R_6") (class "Default")
      (node (ref "A1") (pin "134") (pinfunction "P2[8]__-__CAN_TD2_/_U2_TXD_/_U1_CTS_/_ENET_MDC_/_LCD_VD[2]_/_LCD_VD[6]_134") (pintype "input"))
    )
    (net (code "55") (name "/LCD_R_7") (class "Default")
      (node (ref "A1") (pin "132") (pinfunction "P2[9]__-__USB_CONNECT1_/_U2_RXD_/_U4_RXD_/_ENET_MDIO_/_LCD_VD[3]_/_LCD_VD[7]_132") (pintype "input"))
    )
    (net (code "56") (name "/LCD_VSYNC") (class "Default")
      (node (ref "A1") (pin "144") (pinfunction "P2[3]__-__PWM1[4]_/_U1_DCD_/_T2_MAT2_/_TRACEDATA[2]_/_LCD_FP_144") (pintype "input"))
    )
    (net (code "57") (name "/LED_STATUS_BLUE_EN") (class "Default")
      (node (ref "A1") (pin "139") (pinfunction "P4[27]__-__~{EMC_BLS1}_139") (pintype "input"))
    )
    (net (code "58") (name "/LED_STATUS_GREEN_EN") (class "Default")
      (node (ref "A1") (pin "141") (pinfunction "P5[3]__-__U4_RXD_/_I2C0_SCL_141") (pintype "input"))
    )
    (net (code "59") (name "/LED_STATUS_RED_EN") (class "Default")
      (node (ref "A1") (pin "137") (pinfunction "P3[16]__-__EMC_D[16]_137") (pintype "input"))
    )
    (net (code "60") (name "/LIION_CD") (class "Default")
      (node (ref "A1") (pin "19") (pinfunction "P3[30]__-__EMC_D[30]_/_U1_RTS_/_T1_MAT1_19") (pintype "input"))
    )
    (net (code "61") (name "/LIION_CE") (class "Default")
      (node (ref "A1") (pin "25") (pinfunction "P3[31]__-__EMC_D[31]_/_T1_MAT2_25") (pintype "input"))
    )
    (net (code "62") (name "/MIC_LR") (class "Default")
      (node (ref "R66") (pin "2") (pinfunction "2_2") (pintype "passive"))
      (node (ref "R68") (pin "2") (pinfunction "2_2") (pintype "passive"))
    )
    (net (code "63") (name "/PB_RESET") (class "Default")
      (node (ref "A1") (pin "35") (pinfunction "~{RESET}_35") (pintype "input"))
      (node (ref "R25") (pin "2") (pinfunction "2_2") (pintype "passive"))
    )
    (net (code "64") (name "/RAM_A0") (class "Default")
      (node (ref "A1") (pin "75") (pinfunction "P4[0]__-__EMC_A[0]_75") (pintype "input+no_connect"))
    )
    (net (code "65") (name "/RAM_A1") (class "Default")
      (node (ref "A1") (pin "79") (pinfunction "P4[1]__-__EMC_A[1]_79") (pintype "input+no_connect"))
    )
    (net (code "66") (name "/RAM_A2") (class "Default")
      (node (ref "A1") (pin "83") (pinfunction "P4[2]__-__EMC_A[2]_83") (pintype "input+no_connect"))
    )
    (net (code "67") (name "/RAM_A3") (class "Default")
      (node (ref "A1") (pin "97") (pinfunction "P4[3]__-__EMC_A[3]_97") (pintype "input+no_connect"))
    )
    (net (code "68") (name "/RAM_A4") (class "Default")
      (node (ref "A1") (pin "103") (pinfunction "P4[4]__-__EMC_A[4]_103") (pintype "input+no_connect"))
    )
    (net (code "69") (name "/RAM_A5") (class "Default")
      (node (ref "A1") (pin "107") (pinfunction "P4[5]__-__EMC_A[5]_107") (pintype "input+no_connect"))
    )
    (net (code "70") (name "/RAM_A6") (class "Default")
      (node (ref "A1") (pin "113") (pinfunction "P4[6]__-__EMC_A[6]_113") (pintype "input+no_connect"))
    )
    (net (code "71") (name "/RAM_A7") (class "Default")
      (node (ref "A1") (pin "121") (pinfunction "P4[7]__-__EMC_A[7]_121") (pintype "input+no_connect"))
    )
    (net (code "72") (name "/RAM_A8") (class "Default")
      (node (ref "A1") (pin "127") (pinfunction "P4[8]__-__EMC_A[8]_127") (pintype "input+no_connect"))
    )
    (net (code "73") (name "/RAM_A9") (class "Default")
      (node (ref "A1") (pin "131") (pinfunction "P4[9]__-__EMC_A[9]_131") (pintype "input+no_connect"))
    )
    (net (code "74") (name "/RAM_A10") (class "Default")
      (node (ref "A1") (pin "135") (pinfunction "P4[10]__-__EMC_A[10]_135") (pintype "input+no_connect"))
    )
    (net (code "75") (name "/RAM_A11") (class "Default")
      (node (ref "A1") (pin "145") (pinfunction "P4[11]__-__EMC_A[11]_145") (pintype "input+no_connect"))
    )
    (net (code "76") (name "/RAM_BS0") (class "Default")
      (node (ref "A1") (pin "149") (pinfunction "P4[12]__-__EMC_A[12]_149") (pintype "input+no_connect"))
    )
    (net (code "77") (name "/RAM_BS1") (class "Default")
      (node (ref "A1") (pin "155") (pinfunction "P4[13]__-__EMC_A[13]_155") (pintype "input+no_connect"))
    )
    (net (code "78") (name "/RAM_CAS") (class "Default")
      (node (ref "A1") (pin "87") (pinfunction "P2[15]__-__~{EMC_CAS}_87") (pintype "input+no_connect"))
    )
    (net (code "79") (name "/RAM_CKE") (class "Default")
      (node (ref "A1") (pin "53") (pinfunction "P2[24]__-__EMC_CKE0_53") (pintype "input+no_connect"))
    )
    (net (code "80") (name "/RAM_CLK") (class "Default")
      (node (ref "A1") (pin "59") (pinfunction "P2[18]__-__EMC_CLK[0]_59") (pintype "input+no_connect"))
    )
    (net (code "81") (name "/RAM_CS") (class "Default")
      (node (ref "A1") (pin "187") (pinfunction "P4[30]__-__~{EMC_CS0}_187") (pintype "input+no_connect"))
    )
    (net (code "82") (name "/RAM_DQ0") (class "Default")
      (node (ref "A1") (pin "197") (pinfunction "P3[0]__-__EMC_D[0]_197") (pintype "input+no_connect"))
    )
    (net (code "83") (name "/RAM_DQ1") (class "Default")
      (node (ref "A1") (pin "201") (pinfunction "P3[1]__-__EMC_D[1]_201") (pintype "input+no_connect"))
    )
    (net (code "84") (name "/RAM_DQ2") (class "Default")
      (node (ref "A1") (pin "207") (pinfunction "P3[2]__-__EMC_D[2]_207") (pintype "input+no_connect"))
    )
    (net (code "85") (name "/RAM_DQ3") (class "Default")
      (node (ref "A1") (pin "3") (pinfunction "P3[3]__-__EMC_D[3]_3") (pintype "input+no_connect"))
    )
    (net (code "86") (name "/RAM_DQ4") (class "Default")
      (node (ref "A1") (pin "13") (pinfunction "P3[4]__-__EMC_D[4]_13") (pintype "input"))
    )
    (net (code "87") (name "/RAM_DQ5") (class "Default")
      (node (ref "A1") (pin "17") (pinfunction "P3[5]__-__EMC_D[5]_17") (pintype "input+no_connect"))
    )
    (net (code "88") (name "/RAM_DQ6") (class "Default")
      (node (ref "A1") (pin "23") (pinfunction "P3[6]__-__EMC_D[6]_23") (pintype "input"))
    )
    (net (code "89") (name "/RAM_DQ7") (class "Default")
      (node (ref "A1") (pin "27") (pinfunction "P3[7]__-__EMC_D[7]_27") (pintype "input"))
    )
    (net (code "90") (name "/RAM_DQ8") (class "Default")
      (node (ref "A1") (pin "191") (pinfunction "P3[8]__-__EMC_D[8]_191") (pintype "input+no_connect"))
    )
    (net (code "91") (name "/RAM_DQ9") (class "Default")
      (node (ref "A1") (pin "199") (pinfunction "P3[9]__-__EMC_D[9]_199") (pintype "input+no_connect"))
    )
    (net (code "92") (name "/RAM_DQ10") (class "Default")
      (node (ref "A1") (pin "205") (pinfunction "P3[10]__-__EMC_D[10]_205") (pintype "input+no_connect"))
    )
    (net (code "93") (name "/RAM_DQ11") (class "Default")
      (node (ref "A1") (pin "208") (pinfunction "P3[11]__-__EMC_D[11]_208") (pintype "input"))
    )
    (net (code "94") (name "/RAM_DQ12") (class "Default")
      (node (ref "A1") (pin "1") (pinfunction "P3[12]__-__EMC_D[12]_1") (pintype "input+no_connect"))
    )
    (net (code "95") (name "/RAM_DQ13") (class "Default")
      (node (ref "A1") (pin "7") (pinfunction "P3[13]__-__EMC_D[13]_7") (pintype "input+no_connect"))
    )
    (net (code "96") (name "/RAM_DQ14") (class "Default")
      (node (ref "A1") (pin "21") (pinfunction "P3[14]__-__EMC_D[14]_21") (pintype "input"))
    )
    (net (code "97") (name "/RAM_DQ15") (class "Default")
      (node (ref "A1") (pin "28") (pinfunction "P3[15]__-__EMC_D[15]_28") (pintype "input"))
    )
    (net (code "98") (name "/RAM_LDQM") (class "Default")
      (node (ref "A1") (pin "49") (pinfunction "P2[28]__-__EMC_DQM0_49") (pintype "input"))
    )
    (net (code "99") (name "/RAM_RAS") (class "Default")
      (node (ref "A1") (pin "95") (pinfunction "P2[17]__-__~{EMC_RAS}_95") (pintype "input+no_connect"))
    )
    (net (code "100") (name "/RAM_UDQM") (class "Default")
      (node (ref "A1") (pin "43") (pinfunction "P2[29]__-__EMC_DQM1_43") (pintype "input"))
    )
    (net (code "101") (name "/RAM_WE") (class "Default")
      (node (ref "A1") (pin "179") (pinfunction "P4[25]__-__~{EMC_WE}_179") (pintype "input+no_connect"))
    )
    (net (code "102") (name "/SPI0_CLK") (class "Default")
      (node (ref "A1") (pin "128") (pinfunction "P0[15]__-__U1_TXD_/_SSP0_SCK_128") (pintype "input"))
      (node (ref "P5") (pin "1") (pinfunction "PAD_1") (pintype "passive"))
    )
    (net (code "103") (name "/SPI0_MISO") (class "Default")
      (node (ref "A1") (pin "126") (pinfunction "P0[17]__-__U1_CTS_/_SSP0_MISO_126") (pintype "input"))
      (node (ref "P6") (pin "1") (pinfunction "PAD_1") (pintype "passive"))
    )
    (net (code "104") (name "/SPI0_MOSI") (class "Default")
      (node (ref "A1") (pin "124") (pinfunction "P0[18]__-__U1_DCD_/_SSP0_MOSI_124") (pintype "input"))
      (node (ref "P1") (pin "1") (pinfunction "PAD_1") (pintype "passive"))
    )
    (net (code "105") (name "/UART_RX") (class "Default")
      (node (ref "IC14") (pin "21") (pinfunction "TXD_21") (pintype "passive"))
    )
    (net (code "106") (name "/UART_TX") (class "Default")
      (node (ref "IC14") (pin "20") (pinfunction "RXD_20") (pintype "passive"))
    )
    (net (code "107") (name "/USB_GPIO2") (class "Default")
      (node (ref "A1") (pin "185") (pinfunction "P1[2]__-__ENET_TXD2_/_SD_CLK_/_PWM0[1]_185") (pintype "input"))
      (node (ref "IC14") (pin "12") (pinfunction "GPIO.2_/_RS485_12") (pintype "passive"))
    )
    (net (code "108") (name "/USB_GPIO3") (class "Default")
      (node (ref "A1") (pin "186") (pinfunction "P1[10]__-__ENET_RXD1_/_T3_CAP0_186") (pintype "input"))
      (node (ref "IC14") (pin "11") (pinfunction "GPIO.3_/_WAKEUP_11") (pintype "passive"))
    )
    (net (code "109") (name "/VDD_3.0_COIN") (class "Default")
      (node (ref "A1") (pin "38") (pinfunction "VDD_RTC_(VBAT)_38") (pintype "input"))
    )
    (net (code "110") (name "/XTAL_12_1") (class "Default")
      (node (ref "A1") (pin "44") (pinfunction "XTAL1_44") (pintype "input"))
      (node (ref "C74") (pin "1") (pinfunction "1_1") (pintype "passive"))
      (node (ref "Y2") (pin "2") (pinfunction "2_2") (pintype "passive"))
    )
    (net (code "111") (name "/XTAL_12_2") (class "Default")
      (node (ref "A1") (pin "46") (pinfunction "XTAL2_46") (pintype "input"))
      (node (ref "C75") (pin "1") (pinfunction "1_1") (pintype "passive"))
      (node (ref "Y2") (pin "1") (pinfunction "1_1") (pintype "passive"))
    )
    (net (code "112") (name "/XTAL_32_1") (class "Default")
      (node (ref "A1") (pin "34") (pinfunction "RTCX1_34") (pintype "input"))
      (node (ref "C23") (pin "2") (pinfunction "2_2") (pintype "passive"))
      (node (ref "Y1") (pin "1") (pinfunction "CRYSTAL_1_1") (pintype "passive"))
    )
    (net (code "113") (name "/XTAL_32_2") (class "Default")
      (node (ref "A1") (pin "36") (pinfunction "RTCX2_36") (pintype "input"))
      (node (ref "C24") (pin "2") (pinfunction "2_2") (pintype "passive"))
      (node (ref "Y1") (pin "2") (pinfunction "CRYSTAL_2_2") (pintype "passive"))
    )
    (net (code "114") (name "GND") (class "Default")
      (node (ref "A1") (pin "114") (pinfunction "GND_114") (pintype "input"))
      (node (ref "A1") (pin "133") (pinfunction "GND_133") (pintype "input"))
      (node (ref "A1") (pin "148") (pinfunction "GND_148") (pintype "input"))
      (node (ref "A1") (pin "169") (pinfunction "GND_169") (pintype "input"))
      (node (ref "A1") (pin "172") (pinfunction "GND_172") (pintype "input"))
      (node (ref "A1") (pin "189") (pinfunction "GND_189") (pintype "input"))
      (node (ref "A1") (pin "200") (pinfunction "GND_200") (pintype "input"))
      (node (ref "A1") (pin "22") (pinfunction "VSS_22") (pintype "input"))
      (node (ref "A1") (pin "32") (pinfunction "GND_32") (pintype "input"))
      (node (ref "A1") (pin "33") (pinfunction "GND_33") (pintype "input"))
      (node (ref "A1") (pin "63") (pinfunction "GND_63") (pintype "input"))
      (node (ref "A1") (pin "77") (pinfunction "GND_77") (pintype "input"))
      (node (ref "A1") (pin "84") (pinfunction "GND_84") (pintype "input"))
      (node (ref "A1") (pin "93") (pinfunction "GND_93") (pintype "input"))
      (node (ref "C23") (pin "1") (pinfunction "1_1") (pintype "passive"))
      (node (ref "C24") (pin "1") (pinfunction "1_1") (pintype "passive"))
      (node (ref "C30") (pin "1") (pinfunction "1_1") (pintype "passive"))
      (node (ref "C31") (pin "1") (pinfunction "1_1") (pintype "passive"))
      (node (ref "C36") (pin "1") (pinfunction "1_1") (pintype "passive"))
      (node (ref "C37") (pin "1") (pinfunction "1_1") (pintype "passive"))
      (node (ref "C38") (pin "1") (pinfunction "1_1") (pintype "passive"))
      (node (ref "C39") (pin "1") (pinfunction "1_1") (pintype "passive"))
      (node (ref "C40") (pin "1") (pinfunction "1_1") (pintype "passive"))
      (node (ref "C41") (pin "1") (pinfunction "1_1") (pintype "passive"))
      (node (ref "C42") (pin "1") (pinfunction "1_1") (pintype "passive"))
      (node (ref "C43") (pin "1") (pinfunction "1_1") (pintype "passive"))
      (node (ref "C44") (pin "1") (pinfunction "1_1") (pintype "passive"))
      (node (ref "C45") (pin "1") (pinfunction "1_1") (pintype "passive"))
      (node (ref "C46") (pin "1") (pinfunction "1_1") (pintype "passive"))
      (node (ref "C47") (pin "1") (pinfunction "1_1") (pintype "passive"))
      (node (ref "C48") (pin "1") (pinfunction "1_1") (pintype "passive"))
      (node (ref "C49") (pin "1") (pinfunction "1_1") (pintype "passive"))
      (node (ref "C50") (pin "1") (pinfunction "1_1") (pintype "passive"))
      (node (ref "C51") (pin "1") (pinfunction "1_1") (pintype "passive"))
      (node (ref "C56") (pin "2") (pinfunction "2_2") (pintype "passive"))
      (node (ref "C57") (pin "1") (pinfunction "1_1") (pintype "passive"))
      (node (ref "C58") (pin "1") (pinfunction "1_1") (pintype "passive"))
      (node (ref "C59") (pin "1") (pinfunction "1_1") (pintype "passive"))
      (node (ref "C64") (pin "1") (pinfunction "1_1") (pintype "passive"))
      (node (ref "C65") (pin "1") (pinfunction "1_1") (pintype "passive"))
      (node (ref "C70") (pin "1") (pinfunction "1_1") (pintype "passive"))
      (node (ref "C71") (pin "1") (pinfunction "1_1") (pintype "passive"))
      (node (ref "C74") (pin "2") (pinfunction "2_2") (pintype "passive"))
      (node (ref "C75") (pin "2") (pinfunction "2_2") (pintype "passive"))
      (node (ref "C76") (pin "1") (pinfunction "1_1") (pintype "passive"))
      (node (ref "C77") (pin "1") (pinfunction "1_1") (pintype "passive"))
      (node (ref "C80") (pin "1") (pinfunction "1_1") (pintype "passive"))
      (node (ref "C81") (pin "1") (pinfunction "1_1") (pintype "passive"))
      (node (ref "C84") (pin "1") (pinfunction "1_1") (pintype "passive"))
      (node (ref "C85") (pin "1") (pinfunction "1_1") (pintype "passive"))
      (node (ref "C88") (pin "1") (pinfunction "1_1") (pintype "passive"))
      (node (ref "C89") (pin "1") (pinfunction "1_1") (pintype "passive"))
      (node (ref "IC14") (pin "2") (pinfunction "GND_1_2") (pintype "passive"))
      (node (ref "IC14") (pin "25") (pinfunction "GND_2_25") (pintype "passive"))
      (node (ref "J15") (pin "5") (pinfunction "GND_5") (pintype "passive"))
      (node (ref "J23") (pin "4") (pinfunction "ID_4") (pintype "passive"))
      (node (ref "J23") (pin "5") (pinfunction "GND_5") (pintype "passive"))
      (node (ref "J23") (pin "S") (pinfunction "Shield_S") (pintype "passive"))
      (node (ref "J33") (pin "03") (pinfunction "GND_03") (pintype "passive"))
      (node (ref "J33") (pin "05") (pinfunction "GND_05") (pintype "passive"))
      (node (ref "R102") (pin "2") (pinfunction "2_2") (pintype "passive"))
      (node (ref "R19") (pin "2") (pinfunction "2_2") (pintype "passive"))
      (node (ref "R68") (pin "1") (pinfunction "1_1") (pintype "passive"))
      (node (ref "R94") (pin "2") (pinfunction "2_2") (pintype "passive"))
      (node (ref "R95") (pin "1") (pinfunction "1_1") (pintype "passive"))
      (node (ref "R96") (pin "1") (pinfunction "1_1") (pintype "passive"))
      (node (ref "S4") (pin "3") (pinfunction "3_3") (pintype "passive"))
      (node (ref "S4") (pin "4") (pinfunction "4_4") (pintype "passive"))
    )
    (net (code "115") (name "Net-(A1-JTAG_TCK_(SWDCLK))") (class "Default")
      (node (ref "A1") (pin "10") (pinfunction "JTAG_TCK_(SWDCLK)_10") (pintype "input"))
      (node (ref "J33") (pin "04") (pinfunction "SWCLK_04") (pintype "passive"))
      (node (ref "R9") (pin "1") (pinfunction "1_1") (pintype "passive"))
    )
    (net (code "116") (name "Net-(A1-JTAG_TDI)") (class "Default")
      (node (ref "A1") (pin "4") (pinfunction "JTAG_TDI_4") (pintype "input"))
      (node (ref "J33") (pin "08") (pinfunction "TDI_08") (pintype "passive"))
    )
    (net (code "117") (name "Net-(A1-JTAG_TDO_(SWO))") (class "Default")
      (node (ref "A1") (pin "2") (pinfunction "JTAG_TDO_(SWO)_2") (pintype "input"))
      (node (ref "J33") (pin "06") (pinfunction "SWO_06") (pintype "passive"))
      (node (ref "R13") (pin "1") (pinfunction "1_1") (pintype "passive"))
    )
    (net (code "118") (name "Net-(A1-JTAG_TMS_(SWDIO))") (class "Default")
      (node (ref "A1") (pin "6") (pinfunction "JTAG_TMS_(SWDIO)_6") (pintype "input"))
      (node (ref "J33") (pin "02") (pinfunction "SWDIO_02") (pintype "passive"))
    )
    (net (code "119") (name "Net-(A1-P0[31]__-__USBD+2)") (class "Default")
      (node (ref "A1") (pin "51") (pinfunction "P0[31]__-__USBD+2_51") (pintype "input"))
      (node (ref "R73") (pin "1") (pinfunction "1_1") (pintype "passive"))
    )
    (net (code "120") (name "Net-(A1-P1[18]__-__USB_UP_LED1_{slash}_PWM1[1]_{slash}_T1_CAP0_{slash}_SSP1_MISO)") (class "Default")
      (node (ref "A1") (pin "66") (pinfunction "P1[18]__-__USB_UP_LED1_/_PWM1[1]_/_T1_CAP0_/_SSP1_MISO_66") (pintype "input"))
      (node (ref "D1") (pin "2") (pinfunction "2_2") (pintype "passive"))
    )
    (net (code "121") (name "Net-(A1-P1[30]__-__USB_PWRD2_{slash}_USB_VBUS_{slash}_ADC0_IN[4]_{slash}_I2C0_SDA_{slash}_U3_OE)") (class "Default")
      (node (ref "A1") (pin "42") (pinfunction "P1[30]__-__USB_PWRD2_/_USB_VBUS_/_ADC0_IN[4]_/_I2C0_SDA_/_U3_OE_42") (pintype "input"))
      (node (ref "J15") (pin "1") (pinfunction "VCC_1") (pintype "passive"))
    )
    (net (code "122") (name "Net-(A1-P2[10]__-__~{EINT0}_{slash}_NMI)") (class "Default")
      (node (ref "A1") (pin "110") (pinfunction "P2[10]__-__~{EINT0}_/_NMI_110") (pintype "input"))
      (node (ref "R14") (pin "2") (pinfunction "2_2") (pintype "passive"))
      (node (ref "S4") (pin "1") (pinfunction "1_1") (pintype "passive"))
      (node (ref "S4") (pin "2") (pinfunction "2_2") (pintype "passive"))
    )
    (net (code "123") (name "Net-(A1-P4[21]__-__EMC_A[21]_{slash}_I2C2_SCL_{slash}_SSP1_SSEL)") (class "Default")
      (node (ref "A1") (pin "115") (pinfunction "P4[21]__-__EMC_A[21]_/_I2C2_SCL_/_SSP1_SSEL_115") (pintype "input"))
      (node (ref "R66") (pin "1") (pinfunction "1_1") (pintype "passive"))
    )
    (net (code "124") (name "Net-(A1-USB_D-2)") (class "Default")
      (node (ref "A1") (pin "52") (pinfunction "USB_D-2_52") (pintype "input"))
      (node (ref "R74") (pin "1") (pinfunction "1_1") (pintype "passive"))
    )
    (net (code "125") (name "Net-(D1-Pad1)") (class "Default")
      (node (ref "D1") (pin "1") (pinfunction "1_1") (pintype "passive"))
      (node (ref "R99") (pin "2") (pinfunction "2_2") (pintype "passive"))
    )
    (net (code "126") (name "Net-(D6-Pad1)") (class "Default")
      (node (ref "D6") (pin "1") (pinfunction "1_1") (pintype "passive"))
      (node (ref "R97") (pin "1") (pinfunction "1_1") (pintype "passive"))
    )
    (net (code "127") (name "Net-(D7-Pad1)") (class "Default")
      (node (ref "D7") (pin "1") (pinfunction "1_1") (pintype "passive"))
      (node (ref "R98") (pin "1") (pinfunction "1_1") (pintype "passive"))
    )
    (net (code "128") (name "Net-(IC14-D+)") (class "Default")
      (node (ref "IC14") (pin "3") (pinfunction "D+_3") (pintype "passive"))
      (node (ref "J2") (pin "1") (pinfunction "PAD_1") (pintype "passive"))
      (node (ref "J23") (pin "3") (pinfunction "D+_3") (pintype "passive"))
    )
    (net (code "129") (name "Net-(IC14-D-)") (class "Default")
      (node (ref "IC14") (pin "4") (pinfunction "D-_4") (pintype "passive"))
      (node (ref "J1") (pin "1") (pinfunction "PAD_1") (pintype "passive"))
      (node (ref "J23") (pin "2") (pinfunction "D-_2") (pintype "passive"))
    )
    (net (code "130") (name "Net-(IC14-GPIO.0_{slash}_TXT)") (class "Default")
      (node (ref "D7") (pin "2") (pinfunction "2_2") (pintype "passive"))
      (node (ref "IC14") (pin "14") (pinfunction "GPIO.0_/_TXT_14") (pintype "passive"))
    )
    (net (code "131") (name "Net-(IC14-GPIO.1_{slash}_RXT)") (class "Default")
      (node (ref "D6") (pin "2") (pinfunction "2_2") (pintype "passive"))
      (node (ref "IC14") (pin "13") (pinfunction "GPIO.1_/_RXT_13") (pintype "passive"))
    )
    (net (code "132") (name "Net-(IC14-RSTB)") (class "Default")
      (node (ref "IC14") (pin "9") (pinfunction "RSTB_9") (pintype "passive"))
      (node (ref "R18") (pin "1") (pinfunction "1_1") (pintype "passive"))
    )
    (net (code "133") (name "Net-(IC14-VBUS)") (class "Default")
      (node (ref "IC14") (pin "8") (pinfunction "VBUS_8") (pintype "passive"))
      (node (ref "R20") (pin "2") (pinfunction "2_2") (pintype "passive"))
    )
    (net (code "134") (name "Net-(IC14-VIO)") (class "Default")
      (node (ref "IC14") (pin "5") (pinfunction "VIO_5") (pintype "passive"))
      (node (ref "IC6") (pin "2") (pinfunction "S_2") (pintype "passive"))
    )
    (net (code "135") (name "Net-(J15-D+)") (class "Default")
      (node (ref "J15") (pin "3") (pinfunction "D+_3") (pintype "passive"))
      (node (ref "R73") (pin "2") (pinfunction "2_2") (pintype "passive"))
      (node (ref "R92") (pin "2") (pinfunction "2_2") (pintype "passive"))
    )
    (net (code "136") (name "Net-(J15-D-)") (class "Default")
      (node (ref "J15") (pin "2") (pinfunction "D-_2") (pintype "passive"))
      (node (ref "R74") (pin "2") (pinfunction "2_2") (pintype "passive"))
      (node (ref "R93") (pin "2") (pinfunction "2_2") (pintype "passive"))
    )
    (net (code "137") (name "Net-(J15-Shield)") (class "Default")
      (node (ref "J15") (pin "S") (pinfunction "Shield_S") (pintype "passive"))
      (node (ref "R94") (pin "1") (pinfunction "1_1") (pintype "passive"))
    )
    (net (code "138") (name "Net-(J33-VTref)") (class "Default")
      (node (ref "J33") (pin "01") (pinfunction "VTref_01") (pintype "passive"))
      (node (ref "R6") (pin "1") (pinfunction "1_1") (pintype "passive"))
    )
    (net (code "139") (name "Net-(J33-nRESET)") (class "Default")
      (node (ref "J33") (pin "10") (pinfunction "nRESET_10") (pintype "passive"))
      (node (ref "R25") (pin "1") (pinfunction "1_1") (pintype "passive"))
    )
    (net (code "140") (name "Net-(R92-Pad1)") (class "Default")
      (node (ref "R92") (pin "1") (pinfunction "1_1") (pintype "passive"))
      (node (ref "R96") (pin "2") (pinfunction "2_2") (pintype "passive"))
    )
    (net (code "141") (name "Net-(R93-Pad1)") (class "Default")
      (node (ref "R93") (pin "1") (pinfunction "1_1") (pintype "passive"))
      (node (ref "R95") (pin "2") (pinfunction "2_2") (pintype "passive"))
    )
    (net (code "142") (name "Net-(R100-Pad1)") (class "Default")
      (node (ref "R100") (pin "1") (pinfunction "1_1") (pintype "passive"))
      (node (ref "R99") (pin "1") (pinfunction "1_1") (pintype "passive"))
    )
    (net (code "143") (name "VDD_3.3") (class "Default")
      (node (ref "A1") (pin "112") (pinfunction "VDD_112") (pintype "input"))
      (node (ref "A1") (pin "125") (pinfunction "VDD_125") (pintype "input"))
      (node (ref "A1") (pin "146") (pinfunction "VDD_146") (pintype "input"))
      (node (ref "A1") (pin "15") (pinfunction "VDD_15") (pintype "input"))
      (node (ref "A1") (pin "165") (pinfunction "VDD_165") (pintype "input"))
      (node (ref "A1") (pin "174") (pinfunction "VDD_174") (pintype "input"))
      (node (ref "A1") (pin "181") (pinfunction "VDD_181") (pintype "input"))
      (node (ref "A1") (pin "198") (pinfunction "VDD_198") (pintype "input"))
      (node (ref "A1") (pin "20") (pinfunction "VDD_20") (pintype "input"))
      (node (ref "A1") (pin "24") (pinfunction "VREFP_24") (pintype "input"))
      (node (ref "A1") (pin "26") (pinfunction "VDD_26") (pintype "input"))
      (node (ref "A1") (pin "60") (pinfunction "VDD_60") (pintype "input"))
      (node (ref "A1") (pin "71") (pinfunction "VDD_71") (pintype "input"))
      (node (ref "A1") (pin "86") (pinfunction "VDD_86") (pintype "input"))
      (node (ref "A1") (pin "89") (pinfunction "VDD_89") (pintype "input"))
      (node (ref "C30") (pin "2") (pinfunction "2_2") (pintype "passive"))
      (node (ref "C31") (pin "2") (pinfunction "2_2") (pintype "passive"))
      (node (ref "C36") (pin "2") (pinfunction "2_2") (pintype "passive"))
      (node (ref "C37") (pin "2") (pinfunction "2_2") (pintype "passive"))
      (node (ref "C38") (pin "2") (pinfunction "2_2") (pintype "passive"))
      (node (ref "C39") (pin "2") (pinfunction "2_2") (pintype "passive"))
      (node (ref "C40") (pin "2") (pinfunction "2_2") (pintype "passive"))
      (node (ref "C41") (pin "2") (pinfunction "2_2") (pintype "passive"))
      (node (ref "C42") (pin "2") (pinfunction "2_2") (pintype "passive"))
      (node (ref "C43") (pin "2") (pinfunction "2_2") (pintype "passive"))
      (node (ref "C44") (pin "2") (pinfunction "2_2") (pintype "passive"))
      (node (ref "C45") (pin "2") (pinfunction "2_2") (pintype "passive"))
      (node (ref "C46") (pin "2") (pinfunction "2_2") (pintype "passive"))
      (node (ref "C47") (pin "2") (pinfunction "2_2") (pintype "passive"))
      (node (ref "C50") (pin "2") (pinfunction "2_2") (pintype "passive"))
      (node (ref "C51") (pin "2") (pinfunction "2_2") (pintype "passive"))
      (node (ref "C56") (pin "1") (pinfunction "1_1") (pintype "passive"))
      (node (ref "C57") (pin "2") (pinfunction "2_2") (pintype "passive"))
      (node (ref "C58") (pin "2") (pinfunction "2_2") (pintype "passive"))
      (node (ref "C59") (pin "2") (pinfunction "2_2") (pintype "passive"))
      (node (ref "C64") (pin "2") (pinfunction "2_2") (pintype "passive"))
      (node (ref "C65") (pin "2") (pinfunction "2_2") (pintype "passive"))
      (node (ref "C70") (pin "2") (pinfunction "2_2") (pintype "passive"))
      (node (ref "C71") (pin "2") (pinfunction "2_2") (pintype "passive"))
      (node (ref "C76") (pin "2") (pinfunction "2_2") (pintype "passive"))
      (node (ref "C77") (pin "2") (pinfunction "2_2") (pintype "passive"))
      (node (ref "C80") (pin "2") (pinfunction "2_2") (pintype "passive"))
      (node (ref "C81") (pin "2") (pinfunction "2_2") (pintype "passive"))
      (node (ref "C84") (pin "2") (pinfunction "2_2") (pintype "passive"))
      (node (ref "C85") (pin "2") (pinfunction "2_2") (pintype "passive"))
      (node (ref "C88") (pin "2") (pinfunction "2_2") (pintype "passive"))
      (node (ref "C89") (pin "2") (pinfunction "2_2") (pintype "passive"))
      (node (ref "IC14") (pin "6") (pinfunction "VDD_6") (pintype "passive"))
      (node (ref "IC6") (pin "3") (pinfunction "D_3") (pintype "passive"))
      (node (ref "R100") (pin "2") (pinfunction "2_2") (pintype "passive"))
      (node (ref "R13") (pin "2") (pinfunction "2_2") (pintype "passive"))
      (node (ref "R14") (pin "1") (pinfunction "1_1") (pintype "passive"))
      (node (ref "R18") (pin "2") (pinfunction "2_2") (pintype "passive"))
      (node (ref "R28") (pin "2") (pinfunction "2_2") (pintype "passive"))
      (node (ref "R29") (pin "2") (pinfunction "2_2") (pintype "passive"))
      (node (ref "R31") (pin "2") (pinfunction "2_2") (pintype "passive"))
      (node (ref "R39") (pin "2") (pinfunction "2_2") (pintype "passive"))
      (node (ref "R6") (pin "2") (pinfunction "2_2") (pintype "passive"))
      (node (ref "R9") (pin "2") (pinfunction "2_2") (pintype "passive"))
      (node (ref "R97") (pin "2") (pinfunction "2_2") (pintype "passive"))
      (node (ref "R98") (pin "2") (pinfunction "2_2") (pintype "passive"))
    )
    (net (code "144") (name "VDD_5_USB") (class "Default")
      (node (ref "C48") (pin "2") (pinfunction "2_2") (pintype "passive"))
      (node (ref "C49") (pin "2") (pinfunction "2_2") (pintype "passive"))
      (node (ref "IC14") (pin "7") (pinfunction "VREGIN_7") (pintype "passive"))
      (node (ref "IC6") (pin "1") (pinfunction "G_1") (pintype "passive"))
      (node (ref "J23") (pin "1") (pinfunction "VCC_1") (pintype "passive"))
      (node (ref "R102") (pin "1") (pinfunction "1_1") (pintype "passive"))
      (node (ref "R19") (pin "1") (pinfunction "1_1") (pintype "passive"))
      (node (ref "R20") (pin "1") (pinfunction "1_1") (pintype "passive"))
    )
    (net (code "145") (name "unconnected-(A1-JTAG_~{TRST}-Pad8)") (class "Default")
      (node (ref "A1") (pin "8") (pinfunction "JTAG_~{TRST}_8") (pintype "input+no_connect"))
    )
    (net (code "146") (name "unconnected-(A1-P0[2]__-__U0_TXD_{slash}_U3_TXD-Pad202)") (class "Default")
      (node (ref "A1") (pin "202") (pinfunction "P0[2]__-__U0_TXD_/_U3_TXD_202") (pintype "input+no_connect"))
    )
    (net (code "147") (name "unconnected-(A1-P0[3]__-__U0_RXD_{slash}_U3_RXD-Pad204)") (class "Default")
      (node (ref "A1") (pin "204") (pinfunction "P0[3]__-__U0_RXD_/_U3_RXD_204") (pintype "input+no_connect"))
    )
    (net (code "148") (name "unconnected-(A1-P0[10]__-__U2_TXD_{slash}_I2C2_SDA_{slash}_T3_MAT0-Pad98)") (class "Default")
      (node (ref "A1") (pin "98") (pinfunction "P0[10]__-__U2_TXD_/_I2C2_SDA_/_T3_MAT0_98") (pintype "input+no_connect"))
    )
    (net (code "149") (name "unconnected-(A1-P0[11]__-__U2_RXD_{slash}_I2C2_SCL_{slash}_T2_MAT1-Pad100)") (class "Default")
      (node (ref "A1") (pin "100") (pinfunction "P0[11]__-__U2_RXD_/_I2C2_SCL_/_T2_MAT1_100") (pintype "input+no_connect"))
    )
    (net (code "150") (name "unconnected-(A1-P0[13]__-__USB_UP_LED2_{slash}_SSP1_MOSI_{slash}_ADC0_IN[7]-Pad45)") (class "Default")
      (node (ref "A1") (pin "45") (pinfunction "P0[13]__-__USB_UP_LED2_/_SSP1_MOSI_/_ADC0_IN[7]_45") (pintype "input+no_connect"))
    )
    (net (code "151") (name "unconnected-(A1-P0[14]__-__~{USB_HSTEN2}_{slash}_SSP1_SSEL_{slash}_USB_CONNECT2-Pad69)") (class "Default")
      (node (ref "A1") (pin "69") (pinfunction "P0[14]__-__~{USB_HSTEN2}_/_SSP1_SSEL_/_USB_CONNECT2_69") (pintype "input+no_connect"))
    )
    (net (code "152") (name "unconnected-(A1-P0[29]__-__USB_D+1_{slash}_~{EINT0}-Pad61)") (class "Default")
      (node (ref "A1") (pin "61") (pinfunction "P0[29]__-__USB_D+1_/_~{EINT0}_61") (pintype "input+no_connect"))
    )
    (net (code "153") (name "unconnected-(A1-P0[30]__-__USB_D-1_{slash}_~{EINT1}-Pad62)") (class "Default")
      (node (ref "A1") (pin "62") (pinfunction "P0[30]__-__USB_D-1_/_~{EINT1}_62") (pintype "input+no_connect"))
    )
    (net (code "154") (name "unconnected-(A1-P1[0]__-__ENET_TXD0_{slash}_T3_CAP1_{slash}_SSP2_SCK-Pad196)") (class "Default")
      (node (ref "A1") (pin "196") (pinfunction "P1[0]__-__ENET_TXD0_/_T3_CAP1_/_SSP2_SCK_196") (pintype "input+no_connect"))
    )
    (net (code "155") (name "unconnected-(A1-P1[1]__-__ENET_TXD1_{slash}_T3_MAT3_{slash}_SSP2_MOSI-Pad194)") (class "Default")
      (node (ref "A1") (pin "194") (pinfunction "P1[1]__-__ENET_TXD1_/_T3_MAT3_/_SSP2_MOSI_194") (pintype "input+no_connect"))
    )
    (net (code "156") (name "unconnected-(A1-P1[3]__-__ENET_TXD3_{slash}_SD_CMD_{slash}_PWM0[2]-Pad177)") (class "Default")
      (node (ref "A1") (pin "177") (pinfunction "P1[3]__-__ENET_TXD3_/_SD_CMD_/_PWM0[2]_177") (pintype "input+no_connect"))
    )
    (net (code "157") (name "unconnected-(A1-P1[7]__-__ENET_COL_{slash}_SD_DAT[1]_{slash}_PWM0[5]-Pad153)") (class "Default")
      (node (ref "A1") (pin "153") (pinfunction "P1[7]__-__ENET_COL_/_SD_DAT[1]_/_PWM0[5]_153") (pintype "input+no_connect"))
    )
    (net (code "158") (name "unconnected-(A1-P1[9]__-__ENET_RXD0_{slash}_T3_MAT0-Pad188)") (class "Default")
      (node (ref "A1") (pin "188") (pinfunction "P1[9]__-__ENET_RXD0_/_T3_MAT0_188") (pintype "input+no_connect"))
    )
    (net (code "159") (name "unconnected-(A1-P1[11]__-__ENET_RXD2_{slash}_SD_DAT[2]_{slash}_PWM0[6]-Pad163)") (class "Default")
      (node (ref "A1") (pin "163") (pinfunction "P1[11]__-__ENET_RXD2_/_SD_DAT[2]_/_PWM0[6]_163") (pintype "input+no_connect"))
    )
    (net (code "160") (name "unconnected-(A1-P1[12]__-__ENET_RXD3_{slash}_SD_DAT[3]_{slash}_PWM0_CAP0-Pad157)") (class "Default")
      (node (ref "A1") (pin "157") (pinfunction "P1[12]__-__ENET_RXD3_/_SD_DAT[3]_/_PWM0_CAP0_157") (pintype "input+no_connect"))
    )
    (net (code "161") (name "unconnected-(A1-P1[14]__-__ENET_RX_ER_{slash}_T2_CAP0-Pad184)") (class "Default")
      (node (ref "A1") (pin "184") (pinfunction "P1[14]__-__ENET_RX_ER_/_T2_CAP0_184") (pintype "input+no_connect"))
    )
    (net (code "162") (name "unconnected-(A1-P1[15]__-__ENET_RX_CLK_{slash}_I2C2_SDA-Pad182)") (class "Default")
      (node (ref "A1") (pin "182") (pinfunction "P1[15]__-__ENET_RX_CLK_/_I2C2_SDA_182") (pintype "input+no_connect"))
    )
    (net (code "163") (name "unconnected-(A1-P1[16]__-__ENET_MDC_{slash}_I2S_TX_MCLK-Pad180)") (class "Default")
      (node (ref "A1") (pin "180") (pinfunction "P1[16]__-__ENET_MDC_/_I2S_TX_MCLK_180") (pintype "input+no_connect"))
    )
    (net (code "164") (name "unconnected-(A1-P1[17]__-__ENET_MDIO_{slash}_I2S_RX_MCLK-Pad178)") (class "Default")
      (node (ref "A1") (pin "178") (pinfunction "P1[17]__-__ENET_MDIO_/_I2S_RX_MCLK_178") (pintype "input+no_connect"))
    )
    (net (code "165") (name "unconnected-(A1-P1[19]__-__~{USB_TX_E1}_{slash}_~{USB_PPWR1}_{slash}_T1_CAP1_{slash}_MC_0A_{slash}_SSP1_SCK_{slash}_U2_OE-Pad68)") (class "Default")
      (node (ref "A1") (pin "68") (pinfunction "P1[19]__-__~{USB_TX_E1}_/_~{USB_PPWR1}_/_T1_CAP1_/_MC_0A_/_SSP1_SCK_/_U2_OE_68") (pintype "input+no_connect"))
    )
    (net (code "166") (name "unconnected-(A1-P1[31]__-__~{USB_OVRCR2}_{slash}_SSP1_SCK_{slash}_ADC0_IN[5]_{slash}_I2C0_SCL-Pad40)") (class "Default")
      (node (ref "A1") (pin "40") (pinfunction "P1[31]__-__~{USB_OVRCR2}_/_SSP1_SCK_/_ADC0_IN[5]_/_I2C0_SCL_40") (pintype "input+no_connect"))
    )
    (net (code "167") (name "unconnected-(A1-P2[14]__-__~{EMC_CS2}_{slash}_I2C1_SDA_{slash}_T2_CAP0-Pad91)") (class "Default")
      (node (ref "A1") (pin "91") (pinfunction "P2[14]__-__~{EMC_CS2}_/_I2C1_SDA_/_T2_CAP0_91") (pintype "input+no_connect"))
    )
    (net (code "168") (name "unconnected-(A1-P2[15]__-__~{EMC_CS3}_{slash}_I2C1_SCL_{slash}_T2_CAP1-Pad99)") (class "Default")
      (node (ref "A1") (pin "99") (pinfunction "P2[15]__-__~{EMC_CS3}_/_I2C1_SCL_/_T2_CAP1_99") (pintype "input+no_connect"))
    )
    (net (code "169") (name "unconnected-(A1-P2[19]__-__EMC_CLK[1]-Pad67)") (class "Default")
      (node (ref "A1") (pin "67") (pinfunction "P2[19]__-__EMC_CLK[1]_67") (pintype "input+no_connect"))
    )
    (net (code "170") (name "unconnected-(A1-P2[20]__-__~{EMC_DYCS}0]-Pad73)") (class "Default")
      (node (ref "A1") (pin "73") (pinfunction "P2[20]__-__~{EMC_DYCS}0]_73") (pintype "input+no_connect"))
    )
    (net (code "171") (name "unconnected-(A1-P2[21]__-__~{EMC_DYCS1}-Pad81)") (class "Default")
      (node (ref "A1") (pin "81") (pinfunction "P2[21]__-__~{EMC_DYCS1}_81") (pintype "input+no_connect"))
    )
    (net (code "172") (name "unconnected-(A1-P2[22]__-__~{EMC_DYCS2}_{slash}_SSP0_SCK_{slash}_T2_CAP0-Pad85)") (class "Default")
      (node (ref "A1") (pin "85") (pinfunction "P2[22]__-__~{EMC_DYCS2}_/_SSP0_SCK_/_T2_CAP0_85") (pintype "input+no_connect"))
    )
    (net (code "173") (name "unconnected-(A1-P2[23]__-__~{EMC_DYCS3}_{slash}_SSP0_SSEL_{slash}_T3_CAP1-Pad64)") (class "Default")
      (node (ref "A1") (pin "64") (pinfunction "P2[23]__-__~{EMC_DYCS3}_/_SSP0_SSEL_/_T3_CAP1_64") (pintype "input+no_connect"))
    )
    (net (code "174") (name "unconnected-(A1-P2[26]__-__EMC_CKE2_{slash}_SSP0_MISO_{slash}_T3_MAT0-Pad57)") (class "Default")
      (node (ref "A1") (pin "57") (pinfunction "P2[26]__-__EMC_CKE2_/_SSP0_MISO_/_T3_MAT0_57") (pintype "input+no_connect"))
    )
    (net (code "175") (name "unconnected-(A1-P2[27]__-__EMC_CKE3_{slash}_SSP0_MOSI_{slash}_T3_MAT1-Pad47)") (class "Default")
      (node (ref "A1") (pin "47") (pinfunction "P2[27]__-__EMC_CKE3_/_SSP0_MOSI_/_T3_MAT1_47") (pintype "input+no_connect"))
    )
    (net (code "176") (name "unconnected-(A1-P2[30]__-__EMC_DQM2_{slash}_I2C2_SDA_{slash}_T3_MAT2-Pad31)") (class "Default")
      (node (ref "A1") (pin "31") (pinfunction "P2[30]__-__EMC_DQM2_/_I2C2_SDA_/_T3_MAT2_31") (pintype "input+no_connect"))
    )
    (net (code "177") (name "unconnected-(A1-P2[31]__-__EMC_DQM3_{slash}_I2C2_SCL_{slash}_T3_MAT3-Pad39)") (class "Default")
      (node (ref "A1") (pin "39") (pinfunction "P2[31]__-__EMC_DQM3_/_I2C2_SCL_/_T3_MAT3_39") (pintype "input+no_connect"))
    )
    (net (code "178") (name "unconnected-(A1-P3[17]__-__EMC_D[17]_{slash}_PWM0[2]_{slash}_U1_RXD-Pad143)") (class "Default")
      (node (ref "A1") (pin "143") (pinfunction "P3[17]__-__EMC_D[17]_/_PWM0[2]_/_U1_RXD_143") (pintype "input+no_connect"))
    )
    (net (code "179") (name "unconnected-(A1-P3[19]__-__EMC_D[19]_{slash}_PWM0[4]_{slash}_U1_DCD-Pad161)") (class "Default")
      (node (ref "A1") (pin "161") (pinfunction "P3[19]__-__EMC_D[19]_/_PWM0[4]_/_U1_DCD_161") (pintype "input+no_connect"))
    )
    (net (code "180") (name "unconnected-(A1-P3[20]__-__EMC_D[20]_{slash}_PWM0[5]_{slash}_U1_DSR-Pad167)") (class "Default")
      (node (ref "A1") (pin "167") (pinfunction "P3[20]__-__EMC_D[20]_/_PWM0[5]_/_U1_DSR_167") (pintype "input+no_connect"))
    )
    (net (code "181") (name "unconnected-(A1-P3[21]__-__EMC_D[21]_{slash}_PWM0[6]_{slash}_U1_DTR-Pad175)") (class "Default")
      (node (ref "A1") (pin "175") (pinfunction "P3[21]__-__EMC_D[21]_/_PWM0[6]_/_U1_DTR_175") (pintype "input+no_connect"))
    )
    (net (code "182") (name "unconnected-(A1-P3[22]__-__EMC_D[22]_{slash}_PWM0_CAP0_{slash}_U1_RI-Pad195)") (class "Default")
      (node (ref "A1") (pin "195") (pinfunction "P3[22]__-__EMC_D[22]_/_PWM0_CAP0_/_U1_RI_195") (pintype "input+no_connect"))
    )
    (net (code "183") (name "unconnected-(A1-P3[23]__-__EMC_D[23]_{slash}_PWM1_CAP0_{slash}_T0_CAP0-Pad65)") (class "Default")
      (node (ref "A1") (pin "65") (pinfunction "P3[23]__-__EMC_D[23]_/_PWM1_CAP0_/_T0_CAP0_65") (pintype "input+no_connect"))
    )
    (net (code "184") (name "unconnected-(A1-P3[24]__-__EMC_D[24]_{slash}_PWM1[1]_{slash}_T0_CAP1-Pad58)") (class "Default")
      (node (ref "A1") (pin "58") (pinfunction "P3[24]__-__EMC_D[24]_/_PWM1[1]_/_T0_CAP1_58") (pintype "input+no_connect"))
    )
    (net (code "185") (name "unconnected-(A1-P3[25]__-__EMC_D[25]_{slash}_PWM1[2]_{slash}_T0_MAT0-Pad56)") (class "Default")
      (node (ref "A1") (pin "56") (pinfunction "P3[25]__-__EMC_D[25]_/_PWM1[2]_/_T0_MAT0_56") (pintype "input+no_connect"))
    )
    (net (code "186") (name "unconnected-(A1-P3[26]__-__EMC_D[26]_{slash}_PWM1[3]_{slash}_T0_MAT1_{slash}_STCLK-Pad55)") (class "Default")
      (node (ref "A1") (pin "55") (pinfunction "P3[26]__-__EMC_D[26]_/_PWM1[3]_/_T0_MAT1_/_STCLK_55") (pintype "input+no_connect"))
    )
    (net (code "187") (name "unconnected-(A1-P3[28]__-__EMC_D[28]_{slash}_PWM1[5]_{slash}_T1_CAP1-Pad5)") (class "Default")
      (node (ref "A1") (pin "5") (pinfunction "P3[28]__-__EMC_D[28]_/_PWM1[5]_/_T1_CAP1_5") (pintype "input+no_connect"))
    )
    (net (code "188") (name "unconnected-(A1-P3[29]__-__EMC_D[29]_{slash}_PWM1[6]_{slash}_T1_MAT0-Pad11)") (class "Default")
      (node (ref "A1") (pin "11") (pinfunction "P3[29]__-__EMC_D[29]_/_PWM1[6]_/_T1_MAT0_11") (pintype "input+no_connect"))
    )
    (net (code "189") (name "unconnected-(A1-P4[15]__-__EMC_A[15]-Pad173)") (class "Default")
      (node (ref "A1") (pin "173") (pinfunction "P4[15]__-__EMC_A[15]_173") (pintype "input+no_connect"))
    )
    (net (code "190") (name "unconnected-(A1-P4[16]__-__EMC_A[16]-Pad101)") (class "Default")
      (node (ref "A1") (pin "101") (pinfunction "P4[16]__-__EMC_A[16]_101") (pintype "input+no_connect"))
    )
    (net (code "191") (name "unconnected-(A1-P4[17]__-__EMC_A[17]-Pad104)") (class "Default")
      (node (ref "A1") (pin "104") (pinfunction "P4[17]__-__EMC_A[17]_104") (pintype "input+no_connect"))
    )
    (net (code "192") (name "unconnected-(A1-P4[18]__-__EMC_A[18]-Pad105)") (class "Default")
      (node (ref "A1") (pin "105") (pinfunction "P4[18]__-__EMC_A[18]_105") (pintype "input+no_connect"))
    )
    (net (code "193") (name "unconnected-(A1-P4[19]__-__EMC_A[19]-Pad111)") (class "Default")
      (node (ref "A1") (pin "111") (pinfunction "P4[19]__-__EMC_A[19]_111") (pintype "input+no_connect"))
    )
    (net (code "194") (name "unconnected-(A1-P4[20]__-__EMC_A[20]_{slash}_I2C2_SDA_{slash}_SSP1_SCK-Pad109)") (class "Default")
      (node (ref "A1") (pin "109") (pinfunction "P4[20]__-__EMC_A[20]_/_I2C2_SDA_/_SSP1_SCK_109") (pintype "input+no_connect"))
    )
    (net (code "195") (name "unconnected-(A1-P4[22]__-__EMC_A[22]_{slash}_U2_TXD_{slash}_SSP1_MISO-Pad123)") (class "Default")
      (node (ref "A1") (pin "123") (pinfunction "P4[22]__-__EMC_A[22]_/_U2_TXD_/_SSP1_MISO_123") (pintype "input+no_connect"))
    )
    (net (code "196") (name "unconnected-(A1-P4[23]__-__EMC_A[23]_{slash}_U2_RXD_{slash}_SSP1_MOSI-Pad129)") (class "Default")
      (node (ref "A1") (pin "129") (pinfunction "P4[23]__-__EMC_A[23]_/_U2_RXD_/_SSP1_MOSI_129") (pintype "input+no_connect"))
    )
    (net (code "197") (name "unconnected-(A1-P4[24]__-__~{EMC_OE}-Pad183)") (class "Default")
      (node (ref "A1") (pin "183") (pinfunction "P4[24]__-__~{EMC_OE}_183") (pintype "input+no_connect"))
    )
    (net (code "198") (name "unconnected-(A1-P4[26]__-__~{EMC_BLS0}-Pad119)") (class "Default")
      (node (ref "A1") (pin "119") (pinfunction "P4[26]__-__~{EMC_BLS0}_119") (pintype "input+no_connect"))
    )
    (net (code "199") (name "unconnected-(A1-P5[0]__-__EMC_A[24]_{slash}_SSP2_MOSI_{slash}_T2_MAT2-Pad9)") (class "Default")
      (node (ref "A1") (pin "9") (pinfunction "P5[0]__-__EMC_A[24]_/_SSP2_MOSI_/_T2_MAT2_9") (pintype "input+no_connect"))
    )
    (net (code "200") (name "unconnected-(A1-P5[1]__-__EMC_A[25]_{slash}_SSP2_MISO_{slash}_T2_MAT3-Pad30)") (class "Default")
      (node (ref "A1") (pin "30") (pinfunction "P5[1]__-__EMC_A[25]_/_SSP2_MISO_/_T2_MAT3_30") (pintype "input+no_connect"))
    )
    (net (code "201") (name "unconnected-(A1-P5[2]__-__T3_MAT2_{slash}_I2C0_SDA-Pad117)") (class "Default")
      (node (ref "A1") (pin "117") (pinfunction "P5[2]__-__T3_MAT2_/_I2C0_SDA_117") (pintype "input+no_connect"))
    )
    (net (code "202") (name "unconnected-(A1-RTC_ALARM-Pad37)") (class "Default")
      (node (ref "A1") (pin "37") (pinfunction "RTC_ALARM_37") (pintype "input+no_connect"))
    )
    (net (code "203") (name "unconnected-(A1-~{RSTOUT}-Pad29)") (class "Default")
      (node (ref "A1") (pin "29") (pinfunction "~{RSTOUT}_29") (pintype "input+no_connect"))
    )
    (net (code "204") (name "unconnected-(IC14-CTS-Pad18)") (class "Default")
      (node (ref "IC14") (pin "18") (pinfunction "CTS_18") (pintype "passive"))
    )
    (net (code "205") (name "unconnected-(IC14-DCD-Pad24)") (class "Default")
      (node (ref "IC14") (pin "24") (pinfunction "DCD_24") (pintype "passive"))
    )
    (net (code "206") (name "unconnected-(IC14-DSR-Pad22)") (class "Default")
      (node (ref "IC14") (pin "22") (pinfunction "DSR_22") (pintype "passive"))
    )
    (net (code "207") (name "unconnected-(IC14-DTR-Pad23)") (class "Default")
      (node (ref "IC14") (pin "23") (pinfunction "DTR_23") (pintype "passive"))
    )
    (net (code "208") (name "unconnected-(IC14-NC_1-Pad10)") (class "Default")
      (node (ref "IC14") (pin "10") (pinfunction "NC_1_10") (pintype "passive"))
    )
    (net (code "209") (name "unconnected-(IC14-NC_2-Pad16)") (class "Default")
      (node (ref "IC14") (pin "16") (pinfunction "NC_2_16") (pintype "passive"))
    )
    (net (code "210") (name "unconnected-(IC14-RI_{slash}_CLK-Pad1)") (class "Default")
      (node (ref "IC14") (pin "1") (pinfunction "RI_/_CLK_1") (pintype "passive"))
    )
    (net (code "211") (name "unconnected-(IC14-RTS-Pad19)") (class "Default")
      (node (ref "IC14") (pin "19") (pinfunction "RTS_19") (pintype "passive"))
    )
    (net (code "212") (name "unconnected-(IC14-SUSPEND-Pad17)") (class "Default")
      (node (ref "IC14") (pin "17") (pinfunction "SUSPEND_17") (pintype "passive"))
    )
    (net (code "213") (name "unconnected-(IC14-SUSPENDB-Pad15)") (class "Default")
      (node (ref "IC14") (pin "15") (pinfunction "SUSPENDB_15") (pintype "passive"))
    )
    (net (code "214") (name "unconnected-(J15-ID-Pad4)") (class "Default")
      (node (ref "J15") (pin "4") (pinfunction "ID_4") (pintype "passive"))
    )
    (net (code "215") (name "unconnected-(J33-NC-Pad09)") (class "Default")
      (node (ref "J33") (pin "09") (pinfunction "NC_09") (pintype "passive"))
    )
  )
)
